# DecadeBox_1.net
KiCad netlist of a schematic drawn in Altium Designer
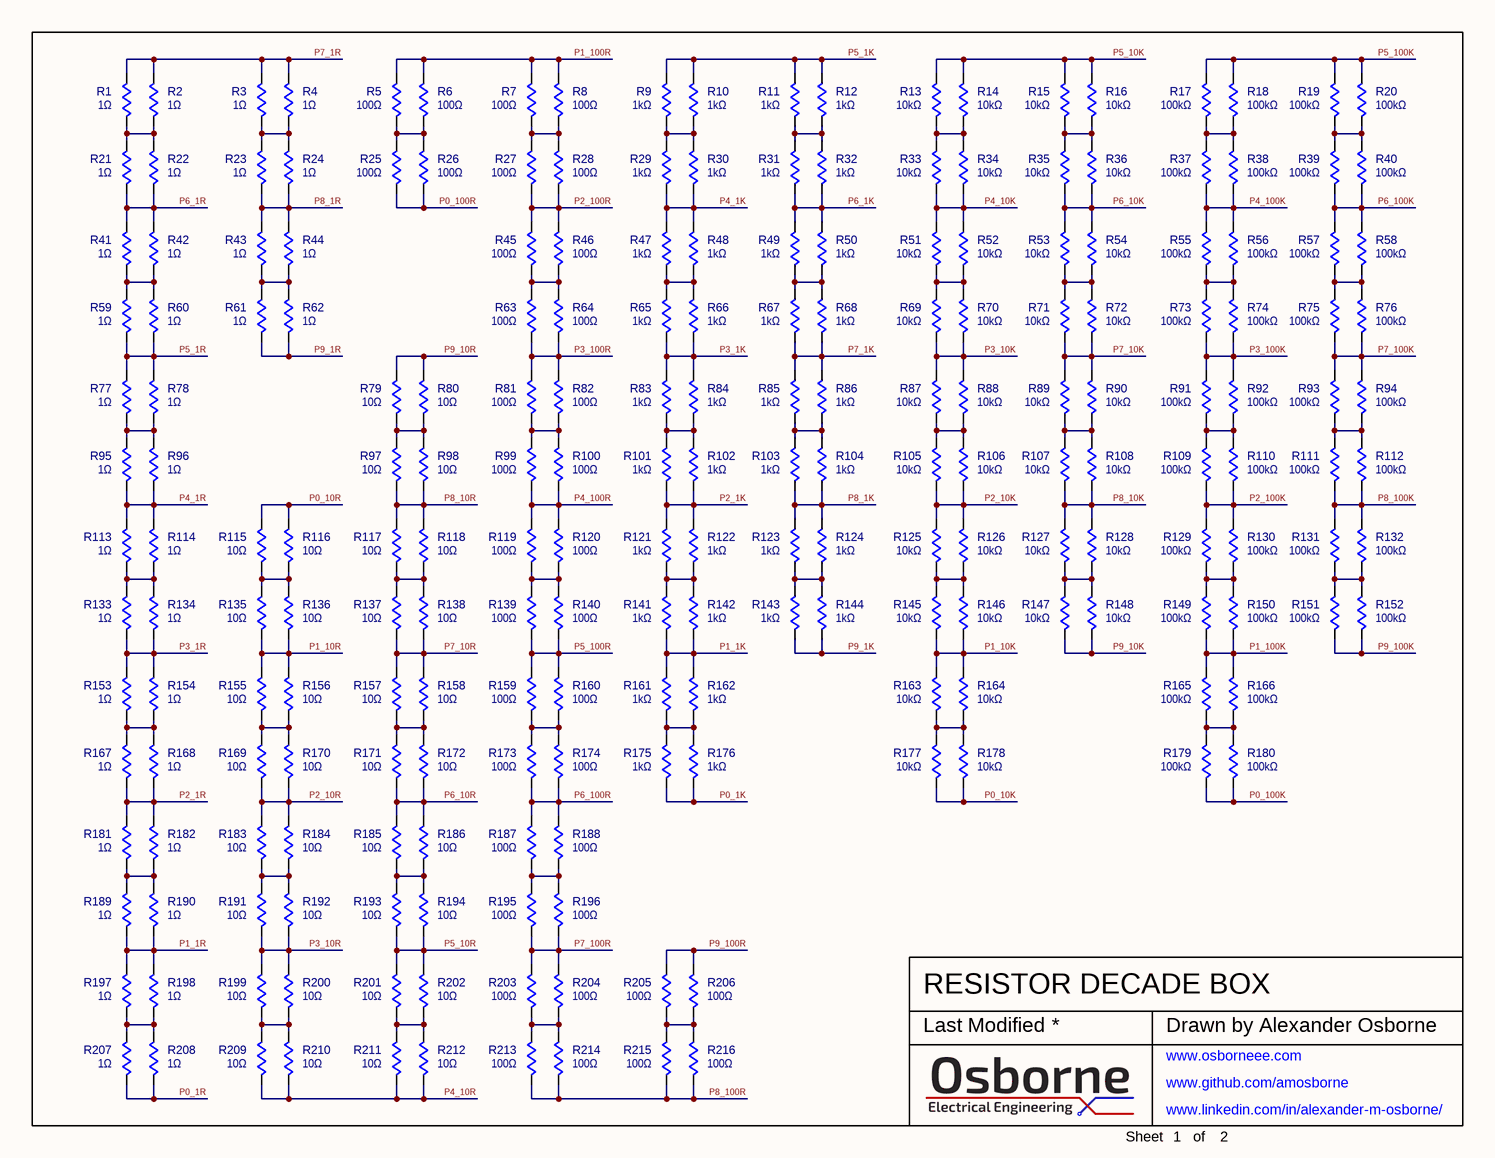
[diagram p0: DecadeBox_1.SchDoc]

(export (version "E")
  (design (tool "Eeschema 10.0.6"))
  (components
    (comp (ref "R1")
      (value "1Ω")
      (footprint "MRS25")
      (description "RES 1Ω 1% 50ppm/K 600mW")
      (fields (field (name "TOLERANCE") "1% + 50ppm/K") (field (name "POWER") "600mW"))
      (libsource (lib "DecadeBox") (part "RES-1OHM"))
    )
    (comp (ref "R2")
      (value "1Ω")
      (footprint "MRS25")
      (description "RES 1Ω 1% 50ppm/K 600mW")
      (fields (field (name "TOLERANCE") "1% + 50ppm/K") (field (name "POWER") "600mW"))
      (libsource (lib "DecadeBox") (part "RES-1OHM"))
    )
    (comp (ref "R3")
      (value "1Ω")
      (footprint "MRS25")
      (description "RES 1Ω 1% 50ppm/K 600mW")
      (fields (field (name "TOLERANCE") "1% + 50ppm/K") (field (name "POWER") "600mW"))
      (libsource (lib "DecadeBox") (part "RES-1OHM"))
    )
    (comp (ref "R4")
      (value "1Ω")
      (footprint "MRS25")
      (description "RES 1Ω 1% 50ppm/K 600mW")
      (fields (field (name "TOLERANCE") "1% + 50ppm/K") (field (name "POWER") "600mW"))
      (libsource (lib "DecadeBox") (part "RES-1OHM"))
    )
    (comp (ref "R5")
      (value "100Ω")
      (footprint "MRS25")
      (description "RES 100Ω 1% 50ppm/K 600mW")
      (fields (field (name "TOLERANCE") "1% + 50ppm/K") (field (name "POWER") "600mW"))
      (libsource (lib "DecadeBox") (part "RES-100OHM"))
    )
    (comp (ref "R6")
      (value "100Ω")
      (footprint "MRS25")
      (description "RES 100Ω 1% 50ppm/K 600mW")
      (fields (field (name "TOLERANCE") "1% + 50ppm/K") (field (name "POWER") "600mW"))
      (libsource (lib "DecadeBox") (part "RES-100OHM"))
    )
    (comp (ref "R7")
      (value "100Ω")
      (footprint "MRS25")
      (description "RES 100Ω 1% 50ppm/K 600mW")
      (fields (field (name "TOLERANCE") "1% + 50ppm/K") (field (name "POWER") "600mW"))
      (libsource (lib "DecadeBox") (part "RES-100OHM"))
    )
    (comp (ref "R8")
      (value "100Ω")
      (footprint "MRS25")
      (description "RES 100Ω 1% 50ppm/K 600mW")
      (fields (field (name "TOLERANCE") "1% + 50ppm/K") (field (name "POWER") "600mW"))
      (libsource (lib "DecadeBox") (part "RES-100OHM"))
    )
    (comp (ref "R9")
      (value "1kΩ")
      (footprint "MRS25")
      (description "RES 1kΩ 1% 50ppm/K 600mW")
      (fields (field (name "TOLERANCE") "1% + 50ppm/K") (field (name "POWER") "600mW"))
      (libsource (lib "DecadeBox") (part "RES-1KOHM"))
    )
    (comp (ref "R10")
      (value "1kΩ")
      (footprint "MRS25")
      (description "RES 1kΩ 1% 50ppm/K 600mW")
      (fields (field (name "TOLERANCE") "1% + 50ppm/K") (field (name "POWER") "600mW"))
      (libsource (lib "DecadeBox") (part "RES-1KOHM"))
    )
    (comp (ref "R11")
      (value "1kΩ")
      (footprint "MRS25")
      (description "RES 1kΩ 1% 50ppm/K 600mW")
      (fields (field (name "TOLERANCE") "1% + 50ppm/K") (field (name "POWER") "600mW"))
      (libsource (lib "DecadeBox") (part "RES-1KOHM"))
    )
    (comp (ref "R12")
      (value "1kΩ")
      (footprint "MRS25")
      (description "RES 1kΩ 1% 50ppm/K 600mW")
      (fields (field (name "TOLERANCE") "1% + 50ppm/K") (field (name "POWER") "600mW"))
      (libsource (lib "DecadeBox") (part "RES-1KOHM"))
    )
    (comp (ref "R13")
      (value "10kΩ")
      (footprint "MRS25")
      (description "RES 10kΩ 1% 50ppm/K 600mW")
      (fields (field (name "TOLERANCE") "1% + 50ppm/K") (field (name "POWER") "600mW"))
      (libsource (lib "DecadeBox") (part "RES-10KOHM"))
    )
    (comp (ref "R14")
      (value "10kΩ")
      (footprint "MRS25")
      (description "RES 10kΩ 1% 50ppm/K 600mW")
      (fields (field (name "TOLERANCE") "1% + 50ppm/K") (field (name "POWER") "600mW"))
      (libsource (lib "DecadeBox") (part "RES-10KOHM"))
    )
    (comp (ref "R15")
      (value "10kΩ")
      (footprint "MRS25")
      (description "RES 10kΩ 1% 50ppm/K 600mW")
      (fields (field (name "TOLERANCE") "1% + 50ppm/K") (field (name "POWER") "600mW"))
      (libsource (lib "DecadeBox") (part "RES-10KOHM"))
    )
    (comp (ref "R16")
      (value "10kΩ")
      (footprint "MRS25")
      (description "RES 10kΩ 1% 50ppm/K 600mW")
      (fields (field (name "TOLERANCE") "1% + 50ppm/K") (field (name "POWER") "600mW"))
      (libsource (lib "DecadeBox") (part "RES-10KOHM"))
    )
    (comp (ref "R17")
      (value "100kΩ")
      (footprint "MRS25")
      (description "RES 100kΩ 1% 50ppm/K 600mW")
      (fields (field (name "TOLERANCE") "1% + 50ppm/K") (field (name "POWER") "600mW"))
      (libsource (lib "DecadeBox") (part "RES-100KOHM"))
    )
    (comp (ref "R18")
      (value "100kΩ")
      (footprint "MRS25")
      (description "RES 100kΩ 1% 50ppm/K 600mW")
      (fields (field (name "TOLERANCE") "1% + 50ppm/K") (field (name "POWER") "600mW"))
      (libsource (lib "DecadeBox") (part "RES-100KOHM"))
    )
    (comp (ref "R19")
      (value "100kΩ")
      (footprint "MRS25")
      (description "RES 100kΩ 1% 50ppm/K 600mW")
      (fields (field (name "TOLERANCE") "1% + 50ppm/K") (field (name "POWER") "600mW"))
      (libsource (lib "DecadeBox") (part "RES-100KOHM"))
    )
    (comp (ref "R20")
      (value "100kΩ")
      (footprint "MRS25")
      (description "RES 100kΩ 1% 50ppm/K 600mW")
      (fields (field (name "TOLERANCE") "1% + 50ppm/K") (field (name "POWER") "600mW"))
      (libsource (lib "DecadeBox") (part "RES-100KOHM"))
    )
    (comp (ref "R21")
      (value "1Ω")
      (footprint "MRS25")
      (description "RES 1Ω 1% 50ppm/K 600mW")
      (fields (field (name "TOLERANCE") "1% + 50ppm/K") (field (name "POWER") "600mW"))
      (libsource (lib "DecadeBox") (part "RES-1OHM"))
    )
    (comp (ref "R22")
      (value "1Ω")
      (footprint "MRS25")
      (description "RES 1Ω 1% 50ppm/K 600mW")
      (fields (field (name "TOLERANCE") "1% + 50ppm/K") (field (name "POWER") "600mW"))
      (libsource (lib "DecadeBox") (part "RES-1OHM"))
    )
    (comp (ref "R23")
      (value "1Ω")
      (footprint "MRS25")
      (description "RES 1Ω 1% 50ppm/K 600mW")
      (fields (field (name "TOLERANCE") "1% + 50ppm/K") (field (name "POWER") "600mW"))
      (libsource (lib "DecadeBox") (part "RES-1OHM"))
    )
    (comp (ref "R24")
      (value "1Ω")
      (footprint "MRS25")
      (description "RES 1Ω 1% 50ppm/K 600mW")
      (fields (field (name "TOLERANCE") "1% + 50ppm/K") (field (name "POWER") "600mW"))
      (libsource (lib "DecadeBox") (part "RES-1OHM"))
    )
    (comp (ref "R25")
      (value "100Ω")
      (footprint "MRS25")
      (description "RES 100Ω 1% 50ppm/K 600mW")
      (fields (field (name "TOLERANCE") "1% + 50ppm/K") (field (name "POWER") "600mW"))
      (libsource (lib "DecadeBox") (part "RES-100OHM"))
    )
    (comp (ref "R26")
      (value "100Ω")
      (footprint "MRS25")
      (description "RES 100Ω 1% 50ppm/K 600mW")
      (fields (field (name "TOLERANCE") "1% + 50ppm/K") (field (name "POWER") "600mW"))
      (libsource (lib "DecadeBox") (part "RES-100OHM"))
    )
    (comp (ref "R27")
      (value "100Ω")
      (footprint "MRS25")
      (description "RES 100Ω 1% 50ppm/K 600mW")
      (fields (field (name "TOLERANCE") "1% + 50ppm/K") (field (name "POWER") "600mW"))
      (libsource (lib "DecadeBox") (part "RES-100OHM"))
    )
    (comp (ref "R28")
      (value "100Ω")
      (footprint "MRS25")
      (description "RES 100Ω 1% 50ppm/K 600mW")
      (fields (field (name "TOLERANCE") "1% + 50ppm/K") (field (name "POWER") "600mW"))
      (libsource (lib "DecadeBox") (part "RES-100OHM"))
    )
    (comp (ref "R29")
      (value "1kΩ")
      (footprint "MRS25")
      (description "RES 1kΩ 1% 50ppm/K 600mW")
      (fields (field (name "TOLERANCE") "1% + 50ppm/K") (field (name "POWER") "600mW"))
      (libsource (lib "DecadeBox") (part "RES-1KOHM"))
    )
    (comp (ref "R30")
      (value "1kΩ")
      (footprint "MRS25")
      (description "RES 1kΩ 1% 50ppm/K 600mW")
      (fields (field (name "TOLERANCE") "1% + 50ppm/K") (field (name "POWER") "600mW"))
      (libsource (lib "DecadeBox") (part "RES-1KOHM"))
    )
    (comp (ref "R31")
      (value "1kΩ")
      (footprint "MRS25")
      (description "RES 1kΩ 1% 50ppm/K 600mW")
      (fields (field (name "TOLERANCE") "1% + 50ppm/K") (field (name "POWER") "600mW"))
      (libsource (lib "DecadeBox") (part "RES-1KOHM"))
    )
    (comp (ref "R32")
      (value "1kΩ")
      (footprint "MRS25")
      (description "RES 1kΩ 1% 50ppm/K 600mW")
      (fields (field (name "TOLERANCE") "1% + 50ppm/K") (field (name "POWER") "600mW"))
      (libsource (lib "DecadeBox") (part "RES-1KOHM"))
    )
    (comp (ref "R33")
      (value "10kΩ")
      (footprint "MRS25")
      (description "RES 10kΩ 1% 50ppm/K 600mW")
      (fields (field (name "TOLERANCE") "1% + 50ppm/K") (field (name "POWER") "600mW"))
      (libsource (lib "DecadeBox") (part "RES-10KOHM"))
    )
    (comp (ref "R34")
      (value "10kΩ")
      (footprint "MRS25")
      (description "RES 10kΩ 1% 50ppm/K 600mW")
      (fields (field (name "TOLERANCE") "1% + 50ppm/K") (field (name "POWER") "600mW"))
      (libsource (lib "DecadeBox") (part "RES-10KOHM"))
    )
    (comp (ref "R35")
      (value "10kΩ")
      (footprint "MRS25")
      (description "RES 10kΩ 1% 50ppm/K 600mW")
      (fields (field (name "TOLERANCE") "1% + 50ppm/K") (field (name "POWER") "600mW"))
      (libsource (lib "DecadeBox") (part "RES-10KOHM"))
    )
    (comp (ref "R36")
      (value "10kΩ")
      (footprint "MRS25")
      (description "RES 10kΩ 1% 50ppm/K 600mW")
      (fields (field (name "TOLERANCE") "1% + 50ppm/K") (field (name "POWER") "600mW"))
      (libsource (lib "DecadeBox") (part "RES-10KOHM"))
    )
    (comp (ref "R37")
      (value "100kΩ")
      (footprint "MRS25")
      (description "RES 100kΩ 1% 50ppm/K 600mW")
      (fields (field (name "TOLERANCE") "1% + 50ppm/K") (field (name "POWER") "600mW"))
      (libsource (lib "DecadeBox") (part "RES-100KOHM"))
    )
    (comp (ref "R38")
      (value "100kΩ")
      (footprint "MRS25")
      (description "RES 100kΩ 1% 50ppm/K 600mW")
      (fields (field (name "TOLERANCE") "1% + 50ppm/K") (field (name "POWER") "600mW"))
      (libsource (lib "DecadeBox") (part "RES-100KOHM"))
    )
    (comp (ref "R39")
      (value "100kΩ")
      (footprint "MRS25")
      (description "RES 100kΩ 1% 50ppm/K 600mW")
      (fields (field (name "TOLERANCE") "1% + 50ppm/K") (field (name "POWER") "600mW"))
      (libsource (lib "DecadeBox") (part "RES-100KOHM"))
    )
    (comp (ref "R40")
      (value "100kΩ")
      (footprint "MRS25")
      (description "RES 100kΩ 1% 50ppm/K 600mW")
      (fields (field (name "TOLERANCE") "1% + 50ppm/K") (field (name "POWER") "600mW"))
      (libsource (lib "DecadeBox") (part "RES-100KOHM"))
    )
    (comp (ref "R41")
      (value "1Ω")
      (footprint "MRS25")
      (description "RES 1Ω 1% 50ppm/K 600mW")
      (fields (field (name "TOLERANCE") "1% + 50ppm/K") (field (name "POWER") "600mW"))
      (libsource (lib "DecadeBox") (part "RES-1OHM"))
    )
    (comp (ref "R42")
      (value "1Ω")
      (footprint "MRS25")
      (description "RES 1Ω 1% 50ppm/K 600mW")
      (fields (field (name "TOLERANCE") "1% + 50ppm/K") (field (name "POWER") "600mW"))
      (libsource (lib "DecadeBox") (part "RES-1OHM"))
    )
    (comp (ref "R43")
      (value "1Ω")
      (footprint "MRS25")
      (description "RES 1Ω 1% 50ppm/K 600mW")
      (fields (field (name "TOLERANCE") "1% + 50ppm/K") (field (name "POWER") "600mW"))
      (libsource (lib "DecadeBox") (part "RES-1OHM"))
    )
    (comp (ref "R44")
      (value "1Ω")
      (footprint "MRS25")
      (description "RES 1Ω 1% 50ppm/K 600mW")
      (fields (field (name "TOLERANCE") "1% + 50ppm/K") (field (name "POWER") "600mW"))
      (libsource (lib "DecadeBox") (part "RES-1OHM"))
    )
    (comp (ref "R45")
      (value "100Ω")
      (footprint "MRS25")
      (description "RES 100Ω 1% 50ppm/K 600mW")
      (fields (field (name "TOLERANCE") "1% + 50ppm/K") (field (name "POWER") "600mW"))
      (libsource (lib "DecadeBox") (part "RES-100OHM"))
    )
    (comp (ref "R46")
      (value "100Ω")
      (footprint "MRS25")
      (description "RES 100Ω 1% 50ppm/K 600mW")
      (fields (field (name "TOLERANCE") "1% + 50ppm/K") (field (name "POWER") "600mW"))
      (libsource (lib "DecadeBox") (part "RES-100OHM"))
    )
    (comp (ref "R47")
      (value "1kΩ")
      (footprint "MRS25")
      (description "RES 1kΩ 1% 50ppm/K 600mW")
      (fields (field (name "TOLERANCE") "1% + 50ppm/K") (field (name "POWER") "600mW"))
      (libsource (lib "DecadeBox") (part "RES-1KOHM"))
    )
    (comp (ref "R48")
      (value "1kΩ")
      (footprint "MRS25")
      (description "RES 1kΩ 1% 50ppm/K 600mW")
      (fields (field (name "TOLERANCE") "1% + 50ppm/K") (field (name "POWER") "600mW"))
      (libsource (lib "DecadeBox") (part "RES-1KOHM"))
    )
    (comp (ref "R49")
      (value "1kΩ")
      (footprint "MRS25")
      (description "RES 1kΩ 1% 50ppm/K 600mW")
      (fields (field (name "TOLERANCE") "1% + 50ppm/K") (field (name "POWER") "600mW"))
      (libsource (lib "DecadeBox") (part "RES-1KOHM"))
    )
    (comp (ref "R50")
      (value "1kΩ")
      (footprint "MRS25")
      (description "RES 1kΩ 1% 50ppm/K 600mW")
      (fields (field (name "TOLERANCE") "1% + 50ppm/K") (field (name "POWER") "600mW"))
      (libsource (lib "DecadeBox") (part "RES-1KOHM"))
    )
    (comp (ref "R51")
      (value "10kΩ")
      (footprint "MRS25")
      (description "RES 10kΩ 1% 50ppm/K 600mW")
      (fields (field (name "TOLERANCE") "1% + 50ppm/K") (field (name "POWER") "600mW"))
      (libsource (lib "DecadeBox") (part "RES-10KOHM"))
    )
    (comp (ref "R52")
      (value "10kΩ")
      (footprint "MRS25")
      (description "RES 10kΩ 1% 50ppm/K 600mW")
      (fields (field (name "TOLERANCE") "1% + 50ppm/K") (field (name "POWER") "600mW"))
      (libsource (lib "DecadeBox") (part "RES-10KOHM"))
    )
    (comp (ref "R53")
      (value "10kΩ")
      (footprint "MRS25")
      (description "RES 10kΩ 1% 50ppm/K 600mW")
      (fields (field (name "TOLERANCE") "1% + 50ppm/K") (field (name "POWER") "600mW"))
      (libsource (lib "DecadeBox") (part "RES-10KOHM"))
    )
    (comp (ref "R54")
      (value "10kΩ")
      (footprint "MRS25")
      (description "RES 10kΩ 1% 50ppm/K 600mW")
      (fields (field (name "TOLERANCE") "1% + 50ppm/K") (field (name "POWER") "600mW"))
      (libsource (lib "DecadeBox") (part "RES-10KOHM"))
    )
    (comp (ref "R55")
      (value "100kΩ")
      (footprint "MRS25")
      (description "RES 100kΩ 1% 50ppm/K 600mW")
      (fields (field (name "TOLERANCE") "1% + 50ppm/K") (field (name "POWER") "600mW"))
      (libsource (lib "DecadeBox") (part "RES-100KOHM"))
    )
    (comp (ref "R56")
      (value "100kΩ")
      (footprint "MRS25")
      (description "RES 100kΩ 1% 50ppm/K 600mW")
      (fields (field (name "TOLERANCE") "1% + 50ppm/K") (field (name "POWER") "600mW"))
      (libsource (lib "DecadeBox") (part "RES-100KOHM"))
    )
    (comp (ref "R57")
      (value "100kΩ")
      (footprint "MRS25")
      (description "RES 100kΩ 1% 50ppm/K 600mW")
      (fields (field (name "TOLERANCE") "1% + 50ppm/K") (field (name "POWER") "600mW"))
      (libsource (lib "DecadeBox") (part "RES-100KOHM"))
    )
    (comp (ref "R58")
      (value "100kΩ")
      (footprint "MRS25")
      (description "RES 100kΩ 1% 50ppm/K 600mW")
      (fields (field (name "TOLERANCE") "1% + 50ppm/K") (field (name "POWER") "600mW"))
      (libsource (lib "DecadeBox") (part "RES-100KOHM"))
    )
    (comp (ref "R59")
      (value "1Ω")
      (footprint "MRS25")
      (description "RES 1Ω 1% 50ppm/K 600mW")
      (fields (field (name "TOLERANCE") "1% + 50ppm/K") (field (name "POWER") "600mW"))
      (libsource (lib "DecadeBox") (part "RES-1OHM"))
    )
    (comp (ref "R60")
      (value "1Ω")
      (footprint "MRS25")
      (description "RES 1Ω 1% 50ppm/K 600mW")
      (fields (field (name "TOLERANCE") "1% + 50ppm/K") (field (name "POWER") "600mW"))
      (libsource (lib "DecadeBox") (part "RES-1OHM"))
    )
    (comp (ref "R61")
      (value "1Ω")
      (footprint "MRS25")
      (description "RES 1Ω 1% 50ppm/K 600mW")
      (fields (field (name "TOLERANCE") "1% + 50ppm/K") (field (name "POWER") "600mW"))
      (libsource (lib "DecadeBox") (part "RES-1OHM"))
    )
    (comp (ref "R62")
      (value "1Ω")
      (footprint "MRS25")
      (description "RES 1Ω 1% 50ppm/K 600mW")
      (fields (field (name "TOLERANCE") "1% + 50ppm/K") (field (name "POWER") "600mW"))
      (libsource (lib "DecadeBox") (part "RES-1OHM"))
    )
    (comp (ref "R63")
      (value "100Ω")
      (footprint "MRS25")
      (description "RES 100Ω 1% 50ppm/K 600mW")
      (fields (field (name "TOLERANCE") "1% + 50ppm/K") (field (name "POWER") "600mW"))
      (libsource (lib "DecadeBox") (part "RES-100OHM"))
    )
    (comp (ref "R64")
      (value "100Ω")
      (footprint "MRS25")
      (description "RES 100Ω 1% 50ppm/K 600mW")
      (fields (field (name "TOLERANCE") "1% + 50ppm/K") (field (name "POWER") "600mW"))
      (libsource (lib "DecadeBox") (part "RES-100OHM"))
    )
    (comp (ref "R65")
      (value "1kΩ")
      (footprint "MRS25")
      (description "RES 1kΩ 1% 50ppm/K 600mW")
      (fields (field (name "TOLERANCE") "1% + 50ppm/K") (field (name "POWER") "600mW"))
      (libsource (lib "DecadeBox") (part "RES-1KOHM"))
    )
    (comp (ref "R66")
      (value "1kΩ")
      (footprint "MRS25")
      (description "RES 1kΩ 1% 50ppm/K 600mW")
      (fields (field (name "TOLERANCE") "1% + 50ppm/K") (field (name "POWER") "600mW"))
      (libsource (lib "DecadeBox") (part "RES-1KOHM"))
    )
    (comp (ref "R67")
      (value "1kΩ")
      (footprint "MRS25")
      (description "RES 1kΩ 1% 50ppm/K 600mW")
      (fields (field (name "TOLERANCE") "1% + 50ppm/K") (field (name "POWER") "600mW"))
      (libsource (lib "DecadeBox") (part "RES-1KOHM"))
    )
    (comp (ref "R68")
      (value "1kΩ")
      (footprint "MRS25")
      (description "RES 1kΩ 1% 50ppm/K 600mW")
      (fields (field (name "TOLERANCE") "1% + 50ppm/K") (field (name "POWER") "600mW"))
      (libsource (lib "DecadeBox") (part "RES-1KOHM"))
    )
    (comp (ref "R69")
      (value "10kΩ")
      (footprint "MRS25")
      (description "RES 10kΩ 1% 50ppm/K 600mW")
      (fields (field (name "TOLERANCE") "1% + 50ppm/K") (field (name "POWER") "600mW"))
      (libsource (lib "DecadeBox") (part "RES-10KOHM"))
    )
    (comp (ref "R70")
      (value "10kΩ")
      (footprint "MRS25")
      (description "RES 10kΩ 1% 50ppm/K 600mW")
      (fields (field (name "TOLERANCE") "1% + 50ppm/K") (field (name "POWER") "600mW"))
      (libsource (lib "DecadeBox") (part "RES-10KOHM"))
    )
    (comp (ref "R71")
      (value "10kΩ")
      (footprint "MRS25")
      (description "RES 10kΩ 1% 50ppm/K 600mW")
      (fields (field (name "TOLERANCE") "1% + 50ppm/K") (field (name "POWER") "600mW"))
      (libsource (lib "DecadeBox") (part "RES-10KOHM"))
    )
    (comp (ref "R72")
      (value "10kΩ")
      (footprint "MRS25")
      (description "RES 10kΩ 1% 50ppm/K 600mW")
      (fields (field (name "TOLERANCE") "1% + 50ppm/K") (field (name "POWER") "600mW"))
      (libsource (lib "DecadeBox") (part "RES-10KOHM"))
    )
    (comp (ref "R73")
      (value "100kΩ")
      (footprint "MRS25")
      (description "RES 100kΩ 1% 50ppm/K 600mW")
      (fields (field (name "TOLERANCE") "1% + 50ppm/K") (field (name "POWER") "600mW"))
      (libsource (lib "DecadeBox") (part "RES-100KOHM"))
    )
    (comp (ref "R74")
      (value "100kΩ")
      (footprint "MRS25")
      (description "RES 100kΩ 1% 50ppm/K 600mW")
      (fields (field (name "TOLERANCE") "1% + 50ppm/K") (field (name "POWER") "600mW"))
      (libsource (lib "DecadeBox") (part "RES-100KOHM"))
    )
    (comp (ref "R75")
      (value "100kΩ")
      (footprint "MRS25")
      (description "RES 100kΩ 1% 50ppm/K 600mW")
      (fields (field (name "TOLERANCE") "1% + 50ppm/K") (field (name "POWER") "600mW"))
      (libsource (lib "DecadeBox") (part "RES-100KOHM"))
    )
    (comp (ref "R76")
      (value "100kΩ")
      (footprint "MRS25")
      (description "RES 100kΩ 1% 50ppm/K 600mW")
      (fields (field (name "TOLERANCE") "1% + 50ppm/K") (field (name "POWER") "600mW"))
      (libsource (lib "DecadeBox") (part "RES-100KOHM"))
    )
    (comp (ref "R77")
      (value "1Ω")
      (footprint "MRS25")
      (description "RES 1Ω 1% 50ppm/K 600mW")
      (fields (field (name "TOLERANCE") "1% + 50ppm/K") (field (name "POWER") "600mW"))
      (libsource (lib "DecadeBox") (part "RES-1OHM"))
    )
    (comp (ref "R78")
      (value "1Ω")
      (footprint "MRS25")
      (description "RES 1Ω 1% 50ppm/K 600mW")
      (fields (field (name "TOLERANCE") "1% + 50ppm/K") (field (name "POWER") "600mW"))
      (libsource (lib "DecadeBox") (part "RES-1OHM"))
    )
    (comp (ref "R79")
      (value "10Ω")
      (footprint "MRS25")
      (description "RES 10Ω 1% 50ppm/K 600mW")
      (fields (field (name "TOLERANCE") "1% + 50ppm/K") (field (name "POWER") "600mW"))
      (libsource (lib "DecadeBox") (part "RES-10OHM"))
    )
    (comp (ref "R80")
      (value "10Ω")
      (footprint "MRS25")
      (description "RES 10Ω 1% 50ppm/K 600mW")
      (fields (field (name "TOLERANCE") "1% + 50ppm/K") (field (name "POWER") "600mW"))
      (libsource (lib "DecadeBox") (part "RES-10OHM"))
    )
    (comp (ref "R81")
      (value "100Ω")
      (footprint "MRS25")
      (description "RES 100Ω 1% 50ppm/K 600mW")
      (fields (field (name "TOLERANCE") "1% + 50ppm/K") (field (name "POWER") "600mW"))
      (libsource (lib "DecadeBox") (part "RES-100OHM"))
    )
    (comp (ref "R82")
      (value "100Ω")
      (footprint "MRS25")
      (description "RES 100Ω 1% 50ppm/K 600mW")
      (fields (field (name "TOLERANCE") "1% + 50ppm/K") (field (name "POWER") "600mW"))
      (libsource (lib "DecadeBox") (part "RES-100OHM"))
    )
    (comp (ref "R83")
      (value "1kΩ")
      (footprint "MRS25")
      (description "RES 1kΩ 1% 50ppm/K 600mW")
      (fields (field (name "TOLERANCE") "1% + 50ppm/K") (field (name "POWER") "600mW"))
      (libsource (lib "DecadeBox") (part "RES-1KOHM"))
    )
    (comp (ref "R84")
      (value "1kΩ")
      (footprint "MRS25")
      (description "RES 1kΩ 1% 50ppm/K 600mW")
      (fields (field (name "TOLERANCE") "1% + 50ppm/K") (field (name "POWER") "600mW"))
      (libsource (lib "DecadeBox") (part "RES-1KOHM"))
    )
    (comp (ref "R85")
      (value "1kΩ")
      (footprint "MRS25")
      (description "RES 1kΩ 1% 50ppm/K 600mW")
      (fields (field (name "TOLERANCE") "1% + 50ppm/K") (field (name "POWER") "600mW"))
      (libsource (lib "DecadeBox") (part "RES-1KOHM"))
    )
    (comp (ref "R86")
      (value "1kΩ")
      (footprint "MRS25")
      (description "RES 1kΩ 1% 50ppm/K 600mW")
      (fields (field (name "TOLERANCE") "1% + 50ppm/K") (field (name "POWER") "600mW"))
      (libsource (lib "DecadeBox") (part "RES-1KOHM"))
    )
    (comp (ref "R87")
      (value "10kΩ")
      (footprint "MRS25")
      (description "RES 10kΩ 1% 50ppm/K 600mW")
      (fields (field (name "TOLERANCE") "1% + 50ppm/K") (field (name "POWER") "600mW"))
      (libsource (lib "DecadeBox") (part "RES-10KOHM"))
    )
    (comp (ref "R88")
      (value "10kΩ")
      (footprint "MRS25")
      (description "RES 10kΩ 1% 50ppm/K 600mW")
      (fields (field (name "TOLERANCE") "1% + 50ppm/K") (field (name "POWER") "600mW"))
      (libsource (lib "DecadeBox") (part "RES-10KOHM"))
    )
    (comp (ref "R89")
      (value "10kΩ")
      (footprint "MRS25")
      (description "RES 10kΩ 1% 50ppm/K 600mW")
      (fields (field (name "TOLERANCE") "1% + 50ppm/K") (field (name "POWER") "600mW"))
      (libsource (lib "DecadeBox") (part "RES-10KOHM"))
    )
    (comp (ref "R90")
      (value "10kΩ")
      (footprint "MRS25")
      (description "RES 10kΩ 1% 50ppm/K 600mW")
      (fields (field (name "TOLERANCE") "1% + 50ppm/K") (field (name "POWER") "600mW"))
      (libsource (lib "DecadeBox") (part "RES-10KOHM"))
    )
    (comp (ref "R91")
      (value "100kΩ")
      (footprint "MRS25")
      (description "RES 100kΩ 1% 50ppm/K 600mW")
      (fields (field (name "TOLERANCE") "1% + 50ppm/K") (field (name "POWER") "600mW"))
      (libsource (lib "DecadeBox") (part "RES-100KOHM"))
    )
    (comp (ref "R92")
      (value "100kΩ")
      (footprint "MRS25")
      (description "RES 100kΩ 1% 50ppm/K 600mW")
      (fields (field (name "TOLERANCE") "1% + 50ppm/K") (field (name "POWER") "600mW"))
      (libsource (lib "DecadeBox") (part "RES-100KOHM"))
    )
    (comp (ref "R93")
      (value "100kΩ")
      (footprint "MRS25")
      (description "RES 100kΩ 1% 50ppm/K 600mW")
      (fields (field (name "TOLERANCE") "1% + 50ppm/K") (field (name "POWER") "600mW"))
      (libsource (lib "DecadeBox") (part "RES-100KOHM"))
    )
    (comp (ref "R94")
      (value "100kΩ")
      (footprint "MRS25")
      (description "RES 100kΩ 1% 50ppm/K 600mW")
      (fields (field (name "TOLERANCE") "1% + 50ppm/K") (field (name "POWER") "600mW"))
      (libsource (lib "DecadeBox") (part "RES-100KOHM"))
    )
    (comp (ref "R95")
      (value "1Ω")
      (footprint "MRS25")
      (description "RES 1Ω 1% 50ppm/K 600mW")
      (fields (field (name "TOLERANCE") "1% + 50ppm/K") (field (name "POWER") "600mW"))
      (libsource (lib "DecadeBox") (part "RES-1OHM"))
    )
    (comp (ref "R96")
      (value "1Ω")
      (footprint "MRS25")
      (description "RES 1Ω 1% 50ppm/K 600mW")
      (fields (field (name "TOLERANCE") "1% + 50ppm/K") (field (name "POWER") "600mW"))
      (libsource (lib "DecadeBox") (part "RES-1OHM"))
    )
    (comp (ref "R97")
      (value "10Ω")
      (footprint "MRS25")
      (description "RES 10Ω 1% 50ppm/K 600mW")
      (fields (field (name "TOLERANCE") "1% + 50ppm/K") (field (name "POWER") "600mW"))
      (libsource (lib "DecadeBox") (part "RES-10OHM"))
    )
    (comp (ref "R98")
      (value "10Ω")
      (footprint "MRS25")
      (description "RES 10Ω 1% 50ppm/K 600mW")
      (fields (field (name "TOLERANCE") "1% + 50ppm/K") (field (name "POWER") "600mW"))
      (libsource (lib "DecadeBox") (part "RES-10OHM"))
    )
    (comp (ref "R99")
      (value "100Ω")
      (footprint "MRS25")
      (description "RES 100Ω 1% 50ppm/K 600mW")
      (fields (field (name "TOLERANCE") "1% + 50ppm/K") (field (name "POWER") "600mW"))
      (libsource (lib "DecadeBox") (part "RES-100OHM"))
    )
    (comp (ref "R100")
      (value "100Ω")
      (footprint "MRS25")
      (description "RES 100Ω 1% 50ppm/K 600mW")
      (fields (field (name "TOLERANCE") "1% + 50ppm/K") (field (name "POWER") "600mW"))
      (libsource (lib "DecadeBox") (part "RES-100OHM"))
    )
    (comp (ref "R101")
      (value "1kΩ")
      (footprint "MRS25")
      (description "RES 1kΩ 1% 50ppm/K 600mW")
      (fields (field (name "TOLERANCE") "1% + 50ppm/K") (field (name "POWER") "600mW"))
      (libsource (lib "DecadeBox") (part "RES-1KOHM"))
    )
    (comp (ref "R102")
      (value "1kΩ")
      (footprint "MRS25")
      (description "RES 1kΩ 1% 50ppm/K 600mW")
      (fields (field (name "TOLERANCE") "1% + 50ppm/K") (field (name "POWER") "600mW"))
      (libsource (lib "DecadeBox") (part "RES-1KOHM"))
    )
    (comp (ref "R103")
      (value "1kΩ")
      (footprint "MRS25")
      (description "RES 1kΩ 1% 50ppm/K 600mW")
      (fields (field (name "TOLERANCE") "1% + 50ppm/K") (field (name "POWER") "600mW"))
      (libsource (lib "DecadeBox") (part "RES-1KOHM"))
    )
    (comp (ref "R104")
      (value "1kΩ")
      (footprint "MRS25")
      (description "RES 1kΩ 1% 50ppm/K 600mW")
      (fields (field (name "TOLERANCE") "1% + 50ppm/K") (field (name "POWER") "600mW"))
      (libsource (lib "DecadeBox") (part "RES-1KOHM"))
    )
    (comp (ref "R105")
      (value "10kΩ")
      (footprint "MRS25")
      (description "RES 10kΩ 1% 50ppm/K 600mW")
      (fields (field (name "TOLERANCE") "1% + 50ppm/K") (field (name "POWER") "600mW"))
      (libsource (lib "DecadeBox") (part "RES-10KOHM"))
    )
    (comp (ref "R106")
      (value "10kΩ")
      (footprint "MRS25")
      (description "RES 10kΩ 1% 50ppm/K 600mW")
      (fields (field (name "TOLERANCE") "1% + 50ppm/K") (field (name "POWER") "600mW"))
      (libsource (lib "DecadeBox") (part "RES-10KOHM"))
    )
    (comp (ref "R107")
      (value "10kΩ")
      (footprint "MRS25")
      (description "RES 10kΩ 1% 50ppm/K 600mW")
      (fields (field (name "TOLERANCE") "1% + 50ppm/K") (field (name "POWER") "600mW"))
      (libsource (lib "DecadeBox") (part "RES-10KOHM"))
    )
    (comp (ref "R108")
      (value "10kΩ")
      (footprint "MRS25")
      (description "RES 10kΩ 1% 50ppm/K 600mW")
      (fields (field (name "TOLERANCE") "1% + 50ppm/K") (field (name "POWER") "600mW"))
      (libsource (lib "DecadeBox") (part "RES-10KOHM"))
    )
    (comp (ref "R109")
      (value "100kΩ")
      (footprint "MRS25")
      (description "RES 100kΩ 1% 50ppm/K 600mW")
      (fields (field (name "TOLERANCE") "1% + 50ppm/K") (field (name "POWER") "600mW"))
      (libsource (lib "DecadeBox") (part "RES-100KOHM"))
    )
    (comp (ref "R110")
      (value "100kΩ")
      (footprint "MRS25")
      (description "RES 100kΩ 1% 50ppm/K 600mW")
      (fields (field (name "TOLERANCE") "1% + 50ppm/K") (field (name "POWER") "600mW"))
      (libsource (lib "DecadeBox") (part "RES-100KOHM"))
    )
    (comp (ref "R111")
      (value "100kΩ")
      (footprint "MRS25")
      (description "RES 100kΩ 1% 50ppm/K 600mW")
      (fields (field (name "TOLERANCE") "1% + 50ppm/K") (field (name "POWER") "600mW"))
      (libsource (lib "DecadeBox") (part "RES-100KOHM"))
    )
    (comp (ref "R112")
      (value "100kΩ")
      (footprint "MRS25")
      (description "RES 100kΩ 1% 50ppm/K 600mW")
      (fields (field (name "TOLERANCE") "1% + 50ppm/K") (field (name "POWER") "600mW"))
      (libsource (lib "DecadeBox") (part "RES-100KOHM"))
    )
    (comp (ref "R113")
      (value "1Ω")
      (footprint "MRS25")
      (description "RES 1Ω 1% 50ppm/K 600mW")
      (fields (field (name "TOLERANCE") "1% + 50ppm/K") (field (name "POWER") "600mW"))
      (libsource (lib "DecadeBox") (part "RES-1OHM"))
    )
    (comp (ref "R114")
      (value "1Ω")
      (footprint "MRS25")
      (description "RES 1Ω 1% 50ppm/K 600mW")
      (fields (field (name "TOLERANCE") "1% + 50ppm/K") (field (name "POWER") "600mW"))
      (libsource (lib "DecadeBox") (part "RES-1OHM"))
    )
    (comp (ref "R115")
      (value "10Ω")
      (footprint "MRS25")
      (description "RES 10Ω 1% 50ppm/K 600mW")
      (fields (field (name "TOLERANCE") "1% + 50ppm/K") (field (name "POWER") "600mW"))
      (libsource (lib "DecadeBox") (part "RES-10OHM"))
    )
    (comp (ref "R116")
      (value "10Ω")
      (footprint "MRS25")
      (description "RES 10Ω 1% 50ppm/K 600mW")
      (fields (field (name "TOLERANCE") "1% + 50ppm/K") (field (name "POWER") "600mW"))
      (libsource (lib "DecadeBox") (part "RES-10OHM"))
    )
    (comp (ref "R117")
      (value "10Ω")
      (footprint "MRS25")
      (description "RES 10Ω 1% 50ppm/K 600mW")
      (fields (field (name "TOLERANCE") "1% + 50ppm/K") (field (name "POWER") "600mW"))
      (libsource (lib "DecadeBox") (part "RES-10OHM"))
    )
    (comp (ref "R118")
      (value "10Ω")
      (footprint "MRS25")
      (description "RES 10Ω 1% 50ppm/K 600mW")
      (fields (field (name "TOLERANCE") "1% + 50ppm/K") (field (name "POWER") "600mW"))
      (libsource (lib "DecadeBox") (part "RES-10OHM"))
    )
    (comp (ref "R119")
      (value "100Ω")
      (footprint "MRS25")
      (description "RES 100Ω 1% 50ppm/K 600mW")
      (fields (field (name "TOLERANCE") "1% + 50ppm/K") (field (name "POWER") "600mW"))
      (libsource (lib "DecadeBox") (part "RES-100OHM"))
    )
    (comp (ref "R120")
      (value "100Ω")
      (footprint "MRS25")
      (description "RES 100Ω 1% 50ppm/K 600mW")
      (fields (field (name "TOLERANCE") "1% + 50ppm/K") (field (name "POWER") "600mW"))
      (libsource (lib "DecadeBox") (part "RES-100OHM"))
    )
    (comp (ref "R121")
      (value "1kΩ")
      (footprint "MRS25")
      (description "RES 1kΩ 1% 50ppm/K 600mW")
      (fields (field (name "TOLERANCE") "1% + 50ppm/K") (field (name "POWER") "600mW"))
      (libsource (lib "DecadeBox") (part "RES-1KOHM"))
    )
    (comp (ref "R122")
      (value "1kΩ")
      (footprint "MRS25")
      (description "RES 1kΩ 1% 50ppm/K 600mW")
      (fields (field (name "TOLERANCE") "1% + 50ppm/K") (field (name "POWER") "600mW"))
      (libsource (lib "DecadeBox") (part "RES-1KOHM"))
    )
    (comp (ref "R123")
      (value "1kΩ")
      (footprint "MRS25")
      (description "RES 1kΩ 1% 50ppm/K 600mW")
      (fields (field (name "TOLERANCE") "1% + 50ppm/K") (field (name "POWER") "600mW"))
      (libsource (lib "DecadeBox") (part "RES-1KOHM"))
    )
    (comp (ref "R124")
      (value "1kΩ")
      (footprint "MRS25")
      (description "RES 1kΩ 1% 50ppm/K 600mW")
      (fields (field (name "TOLERANCE") "1% + 50ppm/K") (field (name "POWER") "600mW"))
      (libsource (lib "DecadeBox") (part "RES-1KOHM"))
    )
    (comp (ref "R125")
      (value "10kΩ")
      (footprint "MRS25")
      (description "RES 10kΩ 1% 50ppm/K 600mW")
      (fields (field (name "TOLERANCE") "1% + 50ppm/K") (field (name "POWER") "600mW"))
      (libsource (lib "DecadeBox") (part "RES-10KOHM"))
    )
    (comp (ref "R126")
      (value "10kΩ")
      (footprint "MRS25")
      (description "RES 10kΩ 1% 50ppm/K 600mW")
      (fields (field (name "TOLERANCE") "1% + 50ppm/K") (field (name "POWER") "600mW"))
      (libsource (lib "DecadeBox") (part "RES-10KOHM"))
    )
    (comp (ref "R127")
      (value "10kΩ")
      (footprint "MRS25")
      (description "RES 10kΩ 1% 50ppm/K 600mW")
      (fields (field (name "TOLERANCE") "1% + 50ppm/K") (field (name "POWER") "600mW"))
      (libsource (lib "DecadeBox") (part "RES-10KOHM"))
    )
    (comp (ref "R128")
      (value "10kΩ")
      (footprint "MRS25")
      (description "RES 10kΩ 1% 50ppm/K 600mW")
      (fields (field (name "TOLERANCE") "1% + 50ppm/K") (field (name "POWER") "600mW"))
      (libsource (lib "DecadeBox") (part "RES-10KOHM"))
    )
    (comp (ref "R129")
      (value "100kΩ")
      (footprint "MRS25")
      (description "RES 100kΩ 1% 50ppm/K 600mW")
      (fields (field (name "TOLERANCE") "1% + 50ppm/K") (field (name "POWER") "600mW"))
      (libsource (lib "DecadeBox") (part "RES-100KOHM"))
    )
    (comp (ref "R130")
      (value "100kΩ")
      (footprint "MRS25")
      (description "RES 100kΩ 1% 50ppm/K 600mW")
      (fields (field (name "TOLERANCE") "1% + 50ppm/K") (field (name "POWER") "600mW"))
      (libsource (lib "DecadeBox") (part "RES-100KOHM"))
    )
    (comp (ref "R131")
      (value "100kΩ")
      (footprint "MRS25")
      (description "RES 100kΩ 1% 50ppm/K 600mW")
      (fields (field (name "TOLERANCE") "1% + 50ppm/K") (field (name "POWER") "600mW"))
      (libsource (lib "DecadeBox") (part "RES-100KOHM"))
    )
    (comp (ref "R132")
      (value "100kΩ")
      (footprint "MRS25")
      (description "RES 100kΩ 1% 50ppm/K 600mW")
      (fields (field (name "TOLERANCE") "1% + 50ppm/K") (field (name "POWER") "600mW"))
      (libsource (lib "DecadeBox") (part "RES-100KOHM"))
    )
    (comp (ref "R133")
      (value "1Ω")
      (footprint "MRS25")
      (description "RES 1Ω 1% 50ppm/K 600mW")
      (fields (field (name "TOLERANCE") "1% + 50ppm/K") (field (name "POWER") "600mW"))
      (libsource (lib "DecadeBox") (part "RES-1OHM"))
    )
    (comp (ref "R134")
      (value "1Ω")
      (footprint "MRS25")
      (description "RES 1Ω 1% 50ppm/K 600mW")
      (fields (field (name "TOLERANCE") "1% + 50ppm/K") (field (name "POWER") "600mW"))
      (libsource (lib "DecadeBox") (part "RES-1OHM"))
    )
    (comp (ref "R135")
      (value "10Ω")
      (footprint "MRS25")
      (description "RES 10Ω 1% 50ppm/K 600mW")
      (fields (field (name "TOLERANCE") "1% + 50ppm/K") (field (name "POWER") "600mW"))
      (libsource (lib "DecadeBox") (part "RES-10OHM"))
    )
    (comp (ref "R136")
      (value "10Ω")
      (footprint "MRS25")
      (description "RES 10Ω 1% 50ppm/K 600mW")
      (fields (field (name "TOLERANCE") "1% + 50ppm/K") (field (name "POWER") "600mW"))
      (libsource (lib "DecadeBox") (part "RES-10OHM"))
    )
    (comp (ref "R137")
      (value "10Ω")
      (footprint "MRS25")
      (description "RES 10Ω 1% 50ppm/K 600mW")
      (fields (field (name "TOLERANCE") "1% + 50ppm/K") (field (name "POWER") "600mW"))
      (libsource (lib "DecadeBox") (part "RES-10OHM"))
    )
    (comp (ref "R138")
      (value "10Ω")
      (footprint "MRS25")
      (description "RES 10Ω 1% 50ppm/K 600mW")
      (fields (field (name "TOLERANCE") "1% + 50ppm/K") (field (name "POWER") "600mW"))
      (libsource (lib "DecadeBox") (part "RES-10OHM"))
    )
    (comp (ref "R139")
      (value "100Ω")
      (footprint "MRS25")
      (description "RES 100Ω 1% 50ppm/K 600mW")
      (fields (field (name "TOLERANCE") "1% + 50ppm/K") (field (name "POWER") "600mW"))
      (libsource (lib "DecadeBox") (part "RES-100OHM"))
    )
    (comp (ref "R140")
      (value "100Ω")
      (footprint "MRS25")
      (description "RES 100Ω 1% 50ppm/K 600mW")
      (fields (field (name "TOLERANCE") "1% + 50ppm/K") (field (name "POWER") "600mW"))
      (libsource (lib "DecadeBox") (part "RES-100OHM"))
    )
    (comp (ref "R141")
      (value "1kΩ")
      (footprint "MRS25")
      (description "RES 1kΩ 1% 50ppm/K 600mW")
      (fields (field (name "TOLERANCE") "1% + 50ppm/K") (field (name "POWER") "600mW"))
      (libsource (lib "DecadeBox") (part "RES-1KOHM"))
    )
    (comp (ref "R142")
      (value "1kΩ")
      (footprint "MRS25")
      (description "RES 1kΩ 1% 50ppm/K 600mW")
      (fields (field (name "TOLERANCE") "1% + 50ppm/K") (field (name "POWER") "600mW"))
      (libsource (lib "DecadeBox") (part "RES-1KOHM"))
    )
    (comp (ref "R143")
      (value "1kΩ")
      (footprint "MRS25")
      (description "RES 1kΩ 1% 50ppm/K 600mW")
      (fields (field (name "TOLERANCE") "1% + 50ppm/K") (field (name "POWER") "600mW"))
      (libsource (lib "DecadeBox") (part "RES-1KOHM"))
    )
    (comp (ref "R144")
      (value "1kΩ")
      (footprint "MRS25")
      (description "RES 1kΩ 1% 50ppm/K 600mW")
      (fields (field (name "TOLERANCE") "1% + 50ppm/K") (field (name "POWER") "600mW"))
      (libsource (lib "DecadeBox") (part "RES-1KOHM"))
    )
    (comp (ref "R145")
      (value "10kΩ")
      (footprint "MRS25")
      (description "RES 10kΩ 1% 50ppm/K 600mW")
      (fields (field (name "TOLERANCE") "1% + 50ppm/K") (field (name "POWER") "600mW"))
      (libsource (lib "DecadeBox") (part "RES-10KOHM"))
    )
    (comp (ref "R146")
      (value "10kΩ")
      (footprint "MRS25")
      (description "RES 10kΩ 1% 50ppm/K 600mW")
      (fields (field (name "TOLERANCE") "1% + 50ppm/K") (field (name "POWER") "600mW"))
      (libsource (lib "DecadeBox") (part "RES-10KOHM"))
    )
    (comp (ref "R147")
      (value "10kΩ")
      (footprint "MRS25")
      (description "RES 10kΩ 1% 50ppm/K 600mW")
      (fields (field (name "TOLERANCE") "1% + 50ppm/K") (field (name "POWER") "600mW"))
      (libsource (lib "DecadeBox") (part "RES-10KOHM"))
    )
    (comp (ref "R148")
      (value "10kΩ")
      (footprint "MRS25")
      (description "RES 10kΩ 1% 50ppm/K 600mW")
      (fields (field (name "TOLERANCE") "1% + 50ppm/K") (field (name "POWER") "600mW"))
      (libsource (lib "DecadeBox") (part "RES-10KOHM"))
    )
    (comp (ref "R149")
      (value "100kΩ")
      (footprint "MRS25")
      (description "RES 100kΩ 1% 50ppm/K 600mW")
      (fields (field (name "TOLERANCE") "1% + 50ppm/K") (field (name "POWER") "600mW"))
      (libsource (lib "DecadeBox") (part "RES-100KOHM"))
    )
    (comp (ref "R150")
      (value "100kΩ")
      (footprint "MRS25")
      (description "RES 100kΩ 1% 50ppm/K 600mW")
      (fields (field (name "TOLERANCE") "1% + 50ppm/K") (field (name "POWER") "600mW"))
      (libsource (lib "DecadeBox") (part "RES-100KOHM"))
    )
    (comp (ref "R151")
      (value "100kΩ")
      (footprint "MRS25")
      (description "RES 100kΩ 1% 50ppm/K 600mW")
      (fields (field (name "TOLERANCE") "1% + 50ppm/K") (field (name "POWER") "600mW"))
      (libsource (lib "DecadeBox") (part "RES-100KOHM"))
    )
    (comp (ref "R152")
      (value "100kΩ")
      (footprint "MRS25")
      (description "RES 100kΩ 1% 50ppm/K 600mW")
      (fields (field (name "TOLERANCE") "1% + 50ppm/K") (field (name "POWER") "600mW"))
      (libsource (lib "DecadeBox") (part "RES-100KOHM"))
    )
    (comp (ref "R153")
      (value "1Ω")
      (footprint "MRS25")
      (description "RES 1Ω 1% 50ppm/K 600mW")
      (fields (field (name "TOLERANCE") "1% + 50ppm/K") (field (name "POWER") "600mW"))
      (libsource (lib "DecadeBox") (part "RES-1OHM"))
    )
    (comp (ref "R154")
      (value "1Ω")
      (footprint "MRS25")
      (description "RES 1Ω 1% 50ppm/K 600mW")
      (fields (field (name "TOLERANCE") "1% + 50ppm/K") (field (name "POWER") "600mW"))
      (libsource (lib "DecadeBox") (part "RES-1OHM"))
    )
    (comp (ref "R155")
      (value "10Ω")
      (footprint "MRS25")
      (description "RES 10Ω 1% 50ppm/K 600mW")
      (fields (field (name "TOLERANCE") "1% + 50ppm/K") (field (name "POWER") "600mW"))
      (libsource (lib "DecadeBox") (part "RES-10OHM"))
    )
    (comp (ref "R156")
      (value "10Ω")
      (footprint "MRS25")
      (description "RES 10Ω 1% 50ppm/K 600mW")
      (fields (field (name "TOLERANCE") "1% + 50ppm/K") (field (name "POWER") "600mW"))
      (libsource (lib "DecadeBox") (part "RES-10OHM"))
    )
    (comp (ref "R157")
      (value "10Ω")
      (footprint "MRS25")
      (description "RES 10Ω 1% 50ppm/K 600mW")
      (fields (field (name "TOLERANCE") "1% + 50ppm/K") (field (name "POWER") "600mW"))
      (libsource (lib "DecadeBox") (part "RES-10OHM"))
    )
    (comp (ref "R158")
      (value "10Ω")
      (footprint "MRS25")
      (description "RES 10Ω 1% 50ppm/K 600mW")
      (fields (field (name "TOLERANCE") "1% + 50ppm/K") (field (name "POWER") "600mW"))
      (libsource (lib "DecadeBox") (part "RES-10OHM"))
    )
    (comp (ref "R159")
      (value "100Ω")
      (footprint "MRS25")
      (description "RES 100Ω 1% 50ppm/K 600mW")
      (fields (field (name "TOLERANCE") "1% + 50ppm/K") (field (name "POWER") "600mW"))
      (libsource (lib "DecadeBox") (part "RES-100OHM"))
    )
    (comp (ref "R160")
      (value "100Ω")
      (footprint "MRS25")
      (description "RES 100Ω 1% 50ppm/K 600mW")
      (fields (field (name "TOLERANCE") "1% + 50ppm/K") (field (name "POWER") "600mW"))
      (libsource (lib "DecadeBox") (part "RES-100OHM"))
    )
    (comp (ref "R161")
      (value "1kΩ")
      (footprint "MRS25")
      (description "RES 1kΩ 1% 50ppm/K 600mW")
      (fields (field (name "TOLERANCE") "1% + 50ppm/K") (field (name "POWER") "600mW"))
      (libsource (lib "DecadeBox") (part "RES-1KOHM"))
    )
    (comp (ref "R162")
      (value "1kΩ")
      (footprint "MRS25")
      (description "RES 1kΩ 1% 50ppm/K 600mW")
      (fields (field (name "TOLERANCE") "1% + 50ppm/K") (field (name "POWER") "600mW"))
      (libsource (lib "DecadeBox") (part "RES-1KOHM"))
    )
    (comp (ref "R163")
      (value "10kΩ")
      (footprint "MRS25")
      (description "RES 10kΩ 1% 50ppm/K 600mW")
      (fields (field (name "TOLERANCE") "1% + 50ppm/K") (field (name "POWER") "600mW"))
      (libsource (lib "DecadeBox") (part "RES-10KOHM"))
    )
    (comp (ref "R164")
      (value "10kΩ")
      (footprint "MRS25")
      (description "RES 10kΩ 1% 50ppm/K 600mW")
      (fields (field (name "TOLERANCE") "1% + 50ppm/K") (field (name "POWER") "600mW"))
      (libsource (lib "DecadeBox") (part "RES-10KOHM"))
    )
    (comp (ref "R165")
      (value "100kΩ")
      (footprint "MRS25")
      (description "RES 100kΩ 1% 50ppm/K 600mW")
      (fields (field (name "TOLERANCE") "1% + 50ppm/K") (field (name "POWER") "600mW"))
      (libsource (lib "DecadeBox") (part "RES-100KOHM"))
    )
    (comp (ref "R166")
      (value "100kΩ")
      (footprint "MRS25")
      (description "RES 100kΩ 1% 50ppm/K 600mW")
      (fields (field (name "TOLERANCE") "1% + 50ppm/K") (field (name "POWER") "600mW"))
      (libsource (lib "DecadeBox") (part "RES-100KOHM"))
    )
    (comp (ref "R167")
      (value "1Ω")
      (footprint "MRS25")
      (description "RES 1Ω 1% 50ppm/K 600mW")
      (fields (field (name "TOLERANCE") "1% + 50ppm/K") (field (name "POWER") "600mW"))
      (libsource (lib "DecadeBox") (part "RES-1OHM"))
    )
    (comp (ref "R168")
      (value "1Ω")
      (footprint "MRS25")
      (description "RES 1Ω 1% 50ppm/K 600mW")
      (fields (field (name "TOLERANCE") "1% + 50ppm/K") (field (name "POWER") "600mW"))
      (libsource (lib "DecadeBox") (part "RES-1OHM"))
    )
    (comp (ref "R169")
      (value "10Ω")
      (footprint "MRS25")
      (description "RES 10Ω 1% 50ppm/K 600mW")
      (fields (field (name "TOLERANCE") "1% + 50ppm/K") (field (name "POWER") "600mW"))
      (libsource (lib "DecadeBox") (part "RES-10OHM"))
    )
    (comp (ref "R170")
      (value "10Ω")
      (footprint "MRS25")
      (description "RES 10Ω 1% 50ppm/K 600mW")
      (fields (field (name "TOLERANCE") "1% + 50ppm/K") (field (name "POWER") "600mW"))
      (libsource (lib "DecadeBox") (part "RES-10OHM"))
    )
    (comp (ref "R171")
      (value "10Ω")
      (footprint "MRS25")
      (description "RES 10Ω 1% 50ppm/K 600mW")
      (fields (field (name "TOLERANCE") "1% + 50ppm/K") (field (name "POWER") "600mW"))
      (libsource (lib "DecadeBox") (part "RES-10OHM"))
    )
    (comp (ref "R172")
      (value "10Ω")
      (footprint "MRS25")
      (description "RES 10Ω 1% 50ppm/K 600mW")
      (fields (field (name "TOLERANCE") "1% + 50ppm/K") (field (name "POWER") "600mW"))
      (libsource (lib "DecadeBox") (part "RES-10OHM"))
    )
    (comp (ref "R173")
      (value "100Ω")
      (footprint "MRS25")
      (description "RES 100Ω 1% 50ppm/K 600mW")
      (fields (field (name "TOLERANCE") "1% + 50ppm/K") (field (name "POWER") "600mW"))
      (libsource (lib "DecadeBox") (part "RES-100OHM"))
    )
    (comp (ref "R174")
      (value "100Ω")
      (footprint "MRS25")
      (description "RES 100Ω 1% 50ppm/K 600mW")
      (fields (field (name "TOLERANCE") "1% + 50ppm/K") (field (name "POWER") "600mW"))
      (libsource (lib "DecadeBox") (part "RES-100OHM"))
    )
    (comp (ref "R175")
      (value "1kΩ")
      (footprint "MRS25")
      (description "RES 1kΩ 1% 50ppm/K 600mW")
      (fields (field (name "TOLERANCE") "1% + 50ppm/K") (field (name "POWER") "600mW"))
      (libsource (lib "DecadeBox") (part "RES-1KOHM"))
    )
    (comp (ref "R176")
      (value "1kΩ")
      (footprint "MRS25")
      (description "RES 1kΩ 1% 50ppm/K 600mW")
      (fields (field (name "TOLERANCE") "1% + 50ppm/K") (field (name "POWER") "600mW"))
      (libsource (lib "DecadeBox") (part "RES-1KOHM"))
    )
    (comp (ref "R177")
      (value "10kΩ")
      (footprint "MRS25")
      (description "RES 10kΩ 1% 50ppm/K 600mW")
      (fields (field (name "TOLERANCE") "1% + 50ppm/K") (field (name "POWER") "600mW"))
      (libsource (lib "DecadeBox") (part "RES-10KOHM"))
    )
    (comp (ref "R178")
      (value "10kΩ")
      (footprint "MRS25")
      (description "RES 10kΩ 1% 50ppm/K 600mW")
      (fields (field (name "TOLERANCE") "1% + 50ppm/K") (field (name "POWER") "600mW"))
      (libsource (lib "DecadeBox") (part "RES-10KOHM"))
    )
    (comp (ref "R179")
      (value "100kΩ")
      (footprint "MRS25")
      (description "RES 100kΩ 1% 50ppm/K 600mW")
      (fields (field (name "TOLERANCE") "1% + 50ppm/K") (field (name "POWER") "600mW"))
      (libsource (lib "DecadeBox") (part "RES-100KOHM"))
    )
    (comp (ref "R180")
      (value "100kΩ")
      (footprint "MRS25")
      (description "RES 100kΩ 1% 50ppm/K 600mW")
      (fields (field (name "TOLERANCE") "1% + 50ppm/K") (field (name "POWER") "600mW"))
      (libsource (lib "DecadeBox") (part "RES-100KOHM"))
    )
    (comp (ref "R181")
      (value "1Ω")
      (footprint "MRS25")
      (description "RES 1Ω 1% 50ppm/K 600mW")
      (fields (field (name "TOLERANCE") "1% + 50ppm/K") (field (name "POWER") "600mW"))
      (libsource (lib "DecadeBox") (part "RES-1OHM"))
    )
    (comp (ref "R182")
      (value "1Ω")
      (footprint "MRS25")
      (description "RES 1Ω 1% 50ppm/K 600mW")
      (fields (field (name "TOLERANCE") "1% + 50ppm/K") (field (name "POWER") "600mW"))
      (libsource (lib "DecadeBox") (part "RES-1OHM"))
    )
    (comp (ref "R183")
      (value "10Ω")
      (footprint "MRS25")
      (description "RES 10Ω 1% 50ppm/K 600mW")
      (fields (field (name "TOLERANCE") "1% + 50ppm/K") (field (name "POWER") "600mW"))
      (libsource (lib "DecadeBox") (part "RES-10OHM"))
    )
    (comp (ref "R184")
      (value "10Ω")
      (footprint "MRS25")
      (description "RES 10Ω 1% 50ppm/K 600mW")
      (fields (field (name "TOLERANCE") "1% + 50ppm/K") (field (name "POWER") "600mW"))
      (libsource (lib "DecadeBox") (part "RES-10OHM"))
    )
    (comp (ref "R185")
      (value "10Ω")
      (footprint "MRS25")
      (description "RES 10Ω 1% 50ppm/K 600mW")
      (fields (field (name "TOLERANCE") "1% + 50ppm/K") (field (name "POWER") "600mW"))
      (libsource (lib "DecadeBox") (part "RES-10OHM"))
    )
    (comp (ref "R186")
      (value "10Ω")
      (footprint "MRS25")
      (description "RES 10Ω 1% 50ppm/K 600mW")
      (fields (field (name "TOLERANCE") "1% + 50ppm/K") (field (name "POWER") "600mW"))
      (libsource (lib "DecadeBox") (part "RES-10OHM"))
    )
    (comp (ref "R187")
      (value "100Ω")
      (footprint "MRS25")
      (description "RES 100Ω 1% 50ppm/K 600mW")
      (fields (field (name "TOLERANCE") "1% + 50ppm/K") (field (name "POWER") "600mW"))
      (libsource (lib "DecadeBox") (part "RES-100OHM"))
    )
    (comp (ref "R188")
      (value "100Ω")
      (footprint "MRS25")
      (description "RES 100Ω 1% 50ppm/K 600mW")
      (fields (field (name "TOLERANCE") "1% + 50ppm/K") (field (name "POWER") "600mW"))
      (libsource (lib "DecadeBox") (part "RES-100OHM"))
    )
    (comp (ref "R189")
      (value "1Ω")
      (footprint "MRS25")
      (description "RES 1Ω 1% 50ppm/K 600mW")
      (fields (field (name "TOLERANCE") "1% + 50ppm/K") (field (name "POWER") "600mW"))
      (libsource (lib "DecadeBox") (part "RES-1OHM"))
    )
    (comp (ref "R190")
      (value "1Ω")
      (footprint "MRS25")
      (description "RES 1Ω 1% 50ppm/K 600mW")
      (fields (field (name "TOLERANCE") "1% + 50ppm/K") (field (name "POWER") "600mW"))
      (libsource (lib "DecadeBox") (part "RES-1OHM"))
    )
    (comp (ref "R191")
      (value "10Ω")
      (footprint "MRS25")
      (description "RES 10Ω 1% 50ppm/K 600mW")
      (fields (field (name "TOLERANCE") "1% + 50ppm/K") (field (name "POWER") "600mW"))
      (libsource (lib "DecadeBox") (part "RES-10OHM"))
    )
    (comp (ref "R192")
      (value "10Ω")
      (footprint "MRS25")
      (description "RES 10Ω 1% 50ppm/K 600mW")
      (fields (field (name "TOLERANCE") "1% + 50ppm/K") (field (name "POWER") "600mW"))
      (libsource (lib "DecadeBox") (part "RES-10OHM"))
    )
    (comp (ref "R193")
      (value "10Ω")
      (footprint "MRS25")
      (description "RES 10Ω 1% 50ppm/K 600mW")
      (fields (field (name "TOLERANCE") "1% + 50ppm/K") (field (name "POWER") "600mW"))
      (libsource (lib "DecadeBox") (part "RES-10OHM"))
    )
    (comp (ref "R194")
      (value "10Ω")
      (footprint "MRS25")
      (description "RES 10Ω 1% 50ppm/K 600mW")
      (fields (field (name "TOLERANCE") "1% + 50ppm/K") (field (name "POWER") "600mW"))
      (libsource (lib "DecadeBox") (part "RES-10OHM"))
    )
    (comp (ref "R195")
      (value "100Ω")
      (footprint "MRS25")
      (description "RES 100Ω 1% 50ppm/K 600mW")
      (fields (field (name "TOLERANCE") "1% + 50ppm/K") (field (name "POWER") "600mW"))
      (libsource (lib "DecadeBox") (part "RES-100OHM"))
    )
    (comp (ref "R196")
      (value "100Ω")
      (footprint "MRS25")
      (description "RES 100Ω 1% 50ppm/K 600mW")
      (fields (field (name "TOLERANCE") "1% + 50ppm/K") (field (name "POWER") "600mW"))
      (libsource (lib "DecadeBox") (part "RES-100OHM"))
    )
    (comp (ref "R197")
      (value "1Ω")
      (footprint "MRS25")
      (description "RES 1Ω 1% 50ppm/K 600mW")
      (fields (field (name "TOLERANCE") "1% + 50ppm/K") (field (name "POWER") "600mW"))
      (libsource (lib "DecadeBox") (part "RES-1OHM"))
    )
    (comp (ref "R198")
      (value "1Ω")
      (footprint "MRS25")
      (description "RES 1Ω 1% 50ppm/K 600mW")
      (fields (field (name "TOLERANCE") "1% + 50ppm/K") (field (name "POWER") "600mW"))
      (libsource (lib "DecadeBox") (part "RES-1OHM"))
    )
    (comp (ref "R199")
      (value "10Ω")
      (footprint "MRS25")
      (description "RES 10Ω 1% 50ppm/K 600mW")
      (fields (field (name "TOLERANCE") "1% + 50ppm/K") (field (name "POWER") "600mW"))
      (libsource (lib "DecadeBox") (part "RES-10OHM"))
    )
    (comp (ref "R200")
      (value "10Ω")
      (footprint "MRS25")
      (description "RES 10Ω 1% 50ppm/K 600mW")
      (fields (field (name "TOLERANCE") "1% + 50ppm/K") (field (name "POWER") "600mW"))
      (libsource (lib "DecadeBox") (part "RES-10OHM"))
    )
    (comp (ref "R201")
      (value "10Ω")
      (footprint "MRS25")
      (description "RES 10Ω 1% 50ppm/K 600mW")
      (fields (field (name "TOLERANCE") "1% + 50ppm/K") (field (name "POWER") "600mW"))
      (libsource (lib "DecadeBox") (part "RES-10OHM"))
    )
    (comp (ref "R202")
      (value "10Ω")
      (footprint "MRS25")
      (description "RES 10Ω 1% 50ppm/K 600mW")
      (fields (field (name "TOLERANCE") "1% + 50ppm/K") (field (name "POWER") "600mW"))
      (libsource (lib "DecadeBox") (part "RES-10OHM"))
    )
    (comp (ref "R203")
      (value "100Ω")
      (footprint "MRS25")
      (description "RES 100Ω 1% 50ppm/K 600mW")
      (fields (field (name "TOLERANCE") "1% + 50ppm/K") (field (name "POWER") "600mW"))
      (libsource (lib "DecadeBox") (part "RES-100OHM"))
    )
    (comp (ref "R204")
      (value "100Ω")
      (footprint "MRS25")
      (description "RES 100Ω 1% 50ppm/K 600mW")
      (fields (field (name "TOLERANCE") "1% + 50ppm/K") (field (name "POWER") "600mW"))
      (libsource (lib "DecadeBox") (part "RES-100OHM"))
    )
    (comp (ref "R205")
      (value "100Ω")
      (footprint "MRS25")
      (description "RES 100Ω 1% 50ppm/K 600mW")
      (fields (field (name "TOLERANCE") "1% + 50ppm/K") (field (name "POWER") "600mW"))
      (libsource (lib "DecadeBox") (part "RES-100OHM"))
    )
    (comp (ref "R206")
      (value "100Ω")
      (footprint "MRS25")
      (description "RES 100Ω 1% 50ppm/K 600mW")
      (fields (field (name "TOLERANCE") "1% + 50ppm/K") (field (name "POWER") "600mW"))
      (libsource (lib "DecadeBox") (part "RES-100OHM"))
    )
    (comp (ref "R207")
      (value "1Ω")
      (footprint "MRS25")
      (description "RES 1Ω 1% 50ppm/K 600mW")
      (fields (field (name "TOLERANCE") "1% + 50ppm/K") (field (name "POWER") "600mW"))
      (libsource (lib "DecadeBox") (part "RES-1OHM"))
    )
    (comp (ref "R208")
      (value "1Ω")
      (footprint "MRS25")
      (description "RES 1Ω 1% 50ppm/K 600mW")
      (fields (field (name "TOLERANCE") "1% + 50ppm/K") (field (name "POWER") "600mW"))
      (libsource (lib "DecadeBox") (part "RES-1OHM"))
    )
    (comp (ref "R209")
      (value "10Ω")
      (footprint "MRS25")
      (description "RES 10Ω 1% 50ppm/K 600mW")
      (fields (field (name "TOLERANCE") "1% + 50ppm/K") (field (name "POWER") "600mW"))
      (libsource (lib "DecadeBox") (part "RES-10OHM"))
    )
    (comp (ref "R210")
      (value "10Ω")
      (footprint "MRS25")
      (description "RES 10Ω 1% 50ppm/K 600mW")
      (fields (field (name "TOLERANCE") "1% + 50ppm/K") (field (name "POWER") "600mW"))
      (libsource (lib "DecadeBox") (part "RES-10OHM"))
    )
    (comp (ref "R211")
      (value "10Ω")
      (footprint "MRS25")
      (description "RES 10Ω 1% 50ppm/K 600mW")
      (fields (field (name "TOLERANCE") "1% + 50ppm/K") (field (name "POWER") "600mW"))
      (libsource (lib "DecadeBox") (part "RES-10OHM"))
    )
    (comp (ref "R212")
      (value "10Ω")
      (footprint "MRS25")
      (description "RES 10Ω 1% 50ppm/K 600mW")
      (fields (field (name "TOLERANCE") "1% + 50ppm/K") (field (name "POWER") "600mW"))
      (libsource (lib "DecadeBox") (part "RES-10OHM"))
    )
    (comp (ref "R213")
      (value "100Ω")
      (footprint "MRS25")
      (description "RES 100Ω 1% 50ppm/K 600mW")
      (fields (field (name "TOLERANCE") "1% + 50ppm/K") (field (name "POWER") "600mW"))
      (libsource (lib "DecadeBox") (part "RES-100OHM"))
    )
    (comp (ref "R214")
      (value "100Ω")
      (footprint "MRS25")
      (description "RES 100Ω 1% 50ppm/K 600mW")
      (fields (field (name "TOLERANCE") "1% + 50ppm/K") (field (name "POWER") "600mW"))
      (libsource (lib "DecadeBox") (part "RES-100OHM"))
    )
    (comp (ref "R215")
      (value "100Ω")
      (footprint "MRS25")
      (description "RES 100Ω 1% 50ppm/K 600mW")
      (fields (field (name "TOLERANCE") "1% + 50ppm/K") (field (name "POWER") "600mW"))
      (libsource (lib "DecadeBox") (part "RES-100OHM"))
    )
    (comp (ref "R216")
      (value "100Ω")
      (footprint "MRS25")
      (description "RES 100Ω 1% 50ppm/K 600mW")
      (fields (field (name "TOLERANCE") "1% + 50ppm/K") (field (name "POWER") "600mW"))
      (libsource (lib "DecadeBox") (part "RES-100OHM"))
    )
  )
  (nets
    (net (code "1") (name "/P0_1K") (class "Default")
      (node (ref "R175") (pin "2") (pintype "passive"))
      (node (ref "R176") (pin "2") (pintype "passive"))
    )
    (net (code "2") (name "/P0_1R") (class "Default")
      (node (ref "R207") (pin "2") (pintype "passive"))
      (node (ref "R208") (pin "2") (pintype "passive"))
    )
    (net (code "3") (name "/P0_10K") (class "Default")
      (node (ref "R177") (pin "2") (pintype "passive"))
      (node (ref "R178") (pin "2") (pintype "passive"))
    )
    (net (code "4") (name "/P0_10R") (class "Default")
      (node (ref "R115") (pin "1") (pintype "passive"))
      (node (ref "R116") (pin "1") (pintype "passive"))
    )
    (net (code "5") (name "/P0_100K") (class "Default")
      (node (ref "R179") (pin "2") (pintype "passive"))
      (node (ref "R180") (pin "2") (pintype "passive"))
    )
    (net (code "6") (name "/P0_100R") (class "Default")
      (node (ref "R25") (pin "2") (pintype "passive"))
      (node (ref "R26") (pin "2") (pintype "passive"))
    )
    (net (code "7") (name "/P1_1K") (class "Default")
      (node (ref "R141") (pin "2") (pintype "passive"))
      (node (ref "R142") (pin "2") (pintype "passive"))
      (node (ref "R161") (pin "1") (pintype "passive"))
      (node (ref "R162") (pin "1") (pintype "passive"))
    )
    (net (code "8") (name "/P1_1R") (class "Default")
      (node (ref "R189") (pin "2") (pintype "passive"))
      (node (ref "R190") (pin "2") (pintype "passive"))
      (node (ref "R197") (pin "1") (pintype "passive"))
      (node (ref "R198") (pin "1") (pintype "passive"))
    )
    (net (code "9") (name "/P1_10K") (class "Default")
      (node (ref "R145") (pin "2") (pintype "passive"))
      (node (ref "R146") (pin "2") (pintype "passive"))
      (node (ref "R163") (pin "1") (pintype "passive"))
      (node (ref "R164") (pin "1") (pintype "passive"))
    )
    (net (code "10") (name "/P1_10R") (class "Default")
      (node (ref "R135") (pin "2") (pintype "passive"))
      (node (ref "R136") (pin "2") (pintype "passive"))
      (node (ref "R155") (pin "1") (pintype "passive"))
      (node (ref "R156") (pin "1") (pintype "passive"))
    )
    (net (code "11") (name "/P1_100K") (class "Default")
      (node (ref "R149") (pin "2") (pintype "passive"))
      (node (ref "R150") (pin "2") (pintype "passive"))
      (node (ref "R165") (pin "1") (pintype "passive"))
      (node (ref "R166") (pin "1") (pintype "passive"))
    )
    (net (code "12") (name "/P1_100R") (class "Default")
      (node (ref "R5") (pin "1") (pintype "passive"))
      (node (ref "R6") (pin "1") (pintype "passive"))
      (node (ref "R7") (pin "1") (pintype "passive"))
      (node (ref "R8") (pin "1") (pintype "passive"))
    )
    (net (code "13") (name "/P2_1K") (class "Default")
      (node (ref "R101") (pin "2") (pintype "passive"))
      (node (ref "R102") (pin "2") (pintype "passive"))
      (node (ref "R121") (pin "1") (pintype "passive"))
      (node (ref "R122") (pin "1") (pintype "passive"))
    )
    (net (code "14") (name "/P2_1R") (class "Default")
      (node (ref "R167") (pin "2") (pintype "passive"))
      (node (ref "R168") (pin "2") (pintype "passive"))
      (node (ref "R181") (pin "1") (pintype "passive"))
      (node (ref "R182") (pin "1") (pintype "passive"))
    )
    (net (code "15") (name "/P2_10K") (class "Default")
      (node (ref "R105") (pin "2") (pintype "passive"))
      (node (ref "R106") (pin "2") (pintype "passive"))
      (node (ref "R125") (pin "1") (pintype "passive"))
      (node (ref "R126") (pin "1") (pintype "passive"))
    )
    (net (code "16") (name "/P2_10R") (class "Default")
      (node (ref "R169") (pin "2") (pintype "passive"))
      (node (ref "R170") (pin "2") (pintype "passive"))
      (node (ref "R183") (pin "1") (pintype "passive"))
      (node (ref "R184") (pin "1") (pintype "passive"))
    )
    (net (code "17") (name "/P2_100K") (class "Default")
      (node (ref "R109") (pin "2") (pintype "passive"))
      (node (ref "R110") (pin "2") (pintype "passive"))
      (node (ref "R129") (pin "1") (pintype "passive"))
      (node (ref "R130") (pin "1") (pintype "passive"))
    )
    (net (code "18") (name "/P2_100R") (class "Default")
      (node (ref "R27") (pin "2") (pintype "passive"))
      (node (ref "R28") (pin "2") (pintype "passive"))
      (node (ref "R45") (pin "1") (pintype "passive"))
      (node (ref "R46") (pin "1") (pintype "passive"))
    )
    (net (code "19") (name "/P3_1K") (class "Default")
      (node (ref "R65") (pin "2") (pintype "passive"))
      (node (ref "R66") (pin "2") (pintype "passive"))
      (node (ref "R83") (pin "1") (pintype "passive"))
      (node (ref "R84") (pin "1") (pintype "passive"))
    )
    (net (code "20") (name "/P3_1R") (class "Default")
      (node (ref "R133") (pin "2") (pintype "passive"))
      (node (ref "R134") (pin "2") (pintype "passive"))
      (node (ref "R153") (pin "1") (pintype "passive"))
      (node (ref "R154") (pin "1") (pintype "passive"))
    )
    (net (code "21") (name "/P3_10K") (class "Default")
      (node (ref "R69") (pin "2") (pintype "passive"))
      (node (ref "R70") (pin "2") (pintype "passive"))
      (node (ref "R87") (pin "1") (pintype "passive"))
      (node (ref "R88") (pin "1") (pintype "passive"))
    )
    (net (code "22") (name "/P3_10R") (class "Default")
      (node (ref "R191") (pin "2") (pintype "passive"))
      (node (ref "R192") (pin "2") (pintype "passive"))
      (node (ref "R199") (pin "1") (pintype "passive"))
      (node (ref "R200") (pin "1") (pintype "passive"))
    )
    (net (code "23") (name "/P3_100K") (class "Default")
      (node (ref "R73") (pin "2") (pintype "passive"))
      (node (ref "R74") (pin "2") (pintype "passive"))
      (node (ref "R91") (pin "1") (pintype "passive"))
      (node (ref "R92") (pin "1") (pintype "passive"))
    )
    (net (code "24") (name "/P3_100R") (class "Default")
      (node (ref "R63") (pin "2") (pintype "passive"))
      (node (ref "R64") (pin "2") (pintype "passive"))
      (node (ref "R81") (pin "1") (pintype "passive"))
      (node (ref "R82") (pin "1") (pintype "passive"))
    )
    (net (code "25") (name "/P4_1K") (class "Default")
      (node (ref "R29") (pin "2") (pintype "passive"))
      (node (ref "R30") (pin "2") (pintype "passive"))
      (node (ref "R47") (pin "1") (pintype "passive"))
      (node (ref "R48") (pin "1") (pintype "passive"))
    )
    (net (code "26") (name "/P4_1R") (class "Default")
      (node (ref "R113") (pin "1") (pintype "passive"))
      (node (ref "R114") (pin "1") (pintype "passive"))
      (node (ref "R95") (pin "2") (pintype "passive"))
      (node (ref "R96") (pin "2") (pintype "passive"))
    )
    (net (code "27") (name "/P4_10K") (class "Default")
      (node (ref "R33") (pin "2") (pintype "passive"))
      (node (ref "R34") (pin "2") (pintype "passive"))
      (node (ref "R51") (pin "1") (pintype "passive"))
      (node (ref "R52") (pin "1") (pintype "passive"))
    )
    (net (code "28") (name "/P4_10R") (class "Default")
      (node (ref "R209") (pin "2") (pintype "passive"))
      (node (ref "R210") (pin "2") (pintype "passive"))
      (node (ref "R211") (pin "2") (pintype "passive"))
      (node (ref "R212") (pin "2") (pintype "passive"))
    )
    (net (code "29") (name "/P4_100K") (class "Default")
      (node (ref "R37") (pin "2") (pintype "passive"))
      (node (ref "R38") (pin "2") (pintype "passive"))
      (node (ref "R55") (pin "1") (pintype "passive"))
      (node (ref "R56") (pin "1") (pintype "passive"))
    )
    (net (code "30") (name "/P4_100R") (class "Default")
      (node (ref "R100") (pin "2") (pintype "passive"))
      (node (ref "R119") (pin "1") (pintype "passive"))
      (node (ref "R120") (pin "1") (pintype "passive"))
      (node (ref "R99") (pin "2") (pintype "passive"))
    )
    (net (code "31") (name "/P5_1K") (class "Default")
      (node (ref "R10") (pin "1") (pintype "passive"))
      (node (ref "R11") (pin "1") (pintype "passive"))
      (node (ref "R12") (pin "1") (pintype "passive"))
      (node (ref "R9") (pin "1") (pintype "passive"))
    )
    (net (code "32") (name "/P5_1R") (class "Default")
      (node (ref "R59") (pin "2") (pintype "passive"))
      (node (ref "R60") (pin "2") (pintype "passive"))
      (node (ref "R77") (pin "1") (pintype "passive"))
      (node (ref "R78") (pin "1") (pintype "passive"))
    )
    (net (code "33") (name "/P5_10K") (class "Default")
      (node (ref "R13") (pin "1") (pintype "passive"))
      (node (ref "R14") (pin "1") (pintype "passive"))
      (node (ref "R15") (pin "1") (pintype "passive"))
      (node (ref "R16") (pin "1") (pintype "passive"))
    )
    (net (code "34") (name "/P5_10R") (class "Default")
      (node (ref "R193") (pin "2") (pintype "passive"))
      (node (ref "R194") (pin "2") (pintype "passive"))
      (node (ref "R201") (pin "1") (pintype "passive"))
      (node (ref "R202") (pin "1") (pintype "passive"))
    )
    (net (code "35") (name "/P5_100K") (class "Default")
      (node (ref "R17") (pin "1") (pintype "passive"))
      (node (ref "R18") (pin "1") (pintype "passive"))
      (node (ref "R19") (pin "1") (pintype "passive"))
      (node (ref "R20") (pin "1") (pintype "passive"))
    )
    (net (code "36") (name "/P5_100R") (class "Default")
      (node (ref "R139") (pin "2") (pintype "passive"))
      (node (ref "R140") (pin "2") (pintype "passive"))
      (node (ref "R159") (pin "1") (pintype "passive"))
      (node (ref "R160") (pin "1") (pintype "passive"))
    )
    (net (code "37") (name "/P6_1K") (class "Default")
      (node (ref "R31") (pin "2") (pintype "passive"))
      (node (ref "R32") (pin "2") (pintype "passive"))
      (node (ref "R49") (pin "1") (pintype "passive"))
      (node (ref "R50") (pin "1") (pintype "passive"))
    )
    (net (code "38") (name "/P6_1R") (class "Default")
      (node (ref "R21") (pin "2") (pintype "passive"))
      (node (ref "R22") (pin "2") (pintype "passive"))
      (node (ref "R41") (pin "1") (pintype "passive"))
      (node (ref "R42") (pin "1") (pintype "passive"))
    )
    (net (code "39") (name "/P6_10K") (class "Default")
      (node (ref "R35") (pin "2") (pintype "passive"))
      (node (ref "R36") (pin "2") (pintype "passive"))
      (node (ref "R53") (pin "1") (pintype "passive"))
      (node (ref "R54") (pin "1") (pintype "passive"))
    )
    (net (code "40") (name "/P6_10R") (class "Default")
      (node (ref "R171") (pin "2") (pintype "passive"))
      (node (ref "R172") (pin "2") (pintype "passive"))
      (node (ref "R185") (pin "1") (pintype "passive"))
      (node (ref "R186") (pin "1") (pintype "passive"))
    )
    (net (code "41") (name "/P6_100K") (class "Default")
      (node (ref "R39") (pin "2") (pintype "passive"))
      (node (ref "R40") (pin "2") (pintype "passive"))
      (node (ref "R57") (pin "1") (pintype "passive"))
      (node (ref "R58") (pin "1") (pintype "passive"))
    )
    (net (code "42") (name "/P6_100R") (class "Default")
      (node (ref "R173") (pin "2") (pintype "passive"))
      (node (ref "R174") (pin "2") (pintype "passive"))
      (node (ref "R187") (pin "1") (pintype "passive"))
      (node (ref "R188") (pin "1") (pintype "passive"))
    )
    (net (code "43") (name "/P7_1K") (class "Default")
      (node (ref "R67") (pin "2") (pintype "passive"))
      (node (ref "R68") (pin "2") (pintype "passive"))
      (node (ref "R85") (pin "1") (pintype "passive"))
      (node (ref "R86") (pin "1") (pintype "passive"))
    )
    (net (code "44") (name "/P7_1R") (class "Default")
      (node (ref "R1") (pin "1") (pintype "passive"))
      (node (ref "R2") (pin "1") (pintype "passive"))
      (node (ref "R3") (pin "1") (pintype "passive"))
      (node (ref "R4") (pin "1") (pintype "passive"))
    )
    (net (code "45") (name "/P7_10K") (class "Default")
      (node (ref "R71") (pin "2") (pintype "passive"))
      (node (ref "R72") (pin "2") (pintype "passive"))
      (node (ref "R89") (pin "1") (pintype "passive"))
      (node (ref "R90") (pin "1") (pintype "passive"))
    )
    (net (code "46") (name "/P7_10R") (class "Default")
      (node (ref "R137") (pin "2") (pintype "passive"))
      (node (ref "R138") (pin "2") (pintype "passive"))
      (node (ref "R157") (pin "1") (pintype "passive"))
      (node (ref "R158") (pin "1") (pintype "passive"))
    )
    (net (code "47") (name "/P7_100K") (class "Default")
      (node (ref "R75") (pin "2") (pintype "passive"))
      (node (ref "R76") (pin "2") (pintype "passive"))
      (node (ref "R93") (pin "1") (pintype "passive"))
      (node (ref "R94") (pin "1") (pintype "passive"))
    )
    (net (code "48") (name "/P7_100R") (class "Default")
      (node (ref "R195") (pin "2") (pintype "passive"))
      (node (ref "R196") (pin "2") (pintype "passive"))
      (node (ref "R203") (pin "1") (pintype "passive"))
      (node (ref "R204") (pin "1") (pintype "passive"))
    )
    (net (code "49") (name "/P8_1K") (class "Default")
      (node (ref "R103") (pin "2") (pintype "passive"))
      (node (ref "R104") (pin "2") (pintype "passive"))
      (node (ref "R123") (pin "1") (pintype "passive"))
      (node (ref "R124") (pin "1") (pintype "passive"))
    )
    (net (code "50") (name "/P8_1R") (class "Default")
      (node (ref "R23") (pin "2") (pintype "passive"))
      (node (ref "R24") (pin "2") (pintype "passive"))
      (node (ref "R43") (pin "1") (pintype "passive"))
      (node (ref "R44") (pin "1") (pintype "passive"))
    )
    (net (code "51") (name "/P8_10K") (class "Default")
      (node (ref "R107") (pin "2") (pintype "passive"))
      (node (ref "R108") (pin "2") (pintype "passive"))
      (node (ref "R127") (pin "1") (pintype "passive"))
      (node (ref "R128") (pin "1") (pintype "passive"))
    )
    (net (code "52") (name "/P8_10R") (class "Default")
      (node (ref "R117") (pin "1") (pintype "passive"))
      (node (ref "R118") (pin "1") (pintype "passive"))
      (node (ref "R97") (pin "2") (pintype "passive"))
      (node (ref "R98") (pin "2") (pintype "passive"))
    )
    (net (code "53") (name "/P8_100K") (class "Default")
      (node (ref "R111") (pin "2") (pintype "passive"))
      (node (ref "R112") (pin "2") (pintype "passive"))
      (node (ref "R131") (pin "1") (pintype "passive"))
      (node (ref "R132") (pin "1") (pintype "passive"))
    )
    (net (code "54") (name "/P8_100R") (class "Default")
      (node (ref "R213") (pin "2") (pintype "passive"))
      (node (ref "R214") (pin "2") (pintype "passive"))
      (node (ref "R215") (pin "2") (pintype "passive"))
      (node (ref "R216") (pin "2") (pintype "passive"))
    )
    (net (code "55") (name "/P9_1K") (class "Default")
      (node (ref "R143") (pin "2") (pintype "passive"))
      (node (ref "R144") (pin "2") (pintype "passive"))
    )
    (net (code "56") (name "/P9_1R") (class "Default")
      (node (ref "R61") (pin "2") (pintype "passive"))
      (node (ref "R62") (pin "2") (pintype "passive"))
    )
    (net (code "57") (name "/P9_10K") (class "Default")
      (node (ref "R147") (pin "2") (pintype "passive"))
      (node (ref "R148") (pin "2") (pintype "passive"))
    )
    (net (code "58") (name "/P9_10R") (class "Default")
      (node (ref "R79") (pin "1") (pintype "passive"))
      (node (ref "R80") (pin "1") (pintype "passive"))
    )
    (net (code "59") (name "/P9_100K") (class "Default")
      (node (ref "R151") (pin "2") (pintype "passive"))
      (node (ref "R152") (pin "2") (pintype "passive"))
    )
    (net (code "60") (name "/P9_100R") (class "Default")
      (node (ref "R205") (pin "1") (pintype "passive"))
      (node (ref "R206") (pin "1") (pintype "passive"))
    )
    (net (code "61") (name "Net-(R1-Pad2)") (class "Default")
      (node (ref "R1") (pin "2") (pintype "passive"))
      (node (ref "R2") (pin "2") (pintype "passive"))
      (node (ref "R21") (pin "1") (pintype "passive"))
      (node (ref "R22") (pin "1") (pintype "passive"))
    )
    (net (code "62") (name "Net-(R10-Pad2)") (class "Default")
      (node (ref "R10") (pin "2") (pintype "passive"))
      (node (ref "R29") (pin "1") (pintype "passive"))
      (node (ref "R30") (pin "1") (pintype "passive"))
      (node (ref "R9") (pin "2") (pintype "passive"))
    )
    (net (code "63") (name "Net-(R11-Pad2)") (class "Default")
      (node (ref "R11") (pin "2") (pintype "passive"))
      (node (ref "R12") (pin "2") (pintype "passive"))
      (node (ref "R31") (pin "1") (pintype "passive"))
      (node (ref "R32") (pin "1") (pintype "passive"))
    )
    (net (code "64") (name "Net-(R13-Pad2)") (class "Default")
      (node (ref "R13") (pin "2") (pintype "passive"))
      (node (ref "R14") (pin "2") (pintype "passive"))
      (node (ref "R33") (pin "1") (pintype "passive"))
      (node (ref "R34") (pin "1") (pintype "passive"))
    )
    (net (code "65") (name "Net-(R15-Pad2)") (class "Default")
      (node (ref "R15") (pin "2") (pintype "passive"))
      (node (ref "R16") (pin "2") (pintype "passive"))
      (node (ref "R35") (pin "1") (pintype "passive"))
      (node (ref "R36") (pin "1") (pintype "passive"))
    )
    (net (code "66") (name "Net-(R17-Pad2)") (class "Default")
      (node (ref "R17") (pin "2") (pintype "passive"))
      (node (ref "R18") (pin "2") (pintype "passive"))
      (node (ref "R37") (pin "1") (pintype "passive"))
      (node (ref "R38") (pin "1") (pintype "passive"))
    )
    (net (code "67") (name "Net-(R19-Pad2)") (class "Default")
      (node (ref "R19") (pin "2") (pintype "passive"))
      (node (ref "R20") (pin "2") (pintype "passive"))
      (node (ref "R39") (pin "1") (pintype "passive"))
      (node (ref "R40") (pin "1") (pintype "passive"))
    )
    (net (code "68") (name "Net-(R23-Pad1)") (class "Default")
      (node (ref "R23") (pin "1") (pintype "passive"))
      (node (ref "R24") (pin "1") (pintype "passive"))
      (node (ref "R3") (pin "2") (pintype "passive"))
      (node (ref "R4") (pin "2") (pintype "passive"))
    )
    (net (code "69") (name "Net-(R25-Pad1)") (class "Default")
      (node (ref "R25") (pin "1") (pintype "passive"))
      (node (ref "R26") (pin "1") (pintype "passive"))
      (node (ref "R5") (pin "2") (pintype "passive"))
      (node (ref "R6") (pin "2") (pintype "passive"))
    )
    (net (code "70") (name "Net-(R27-Pad1)") (class "Default")
      (node (ref "R27") (pin "1") (pintype "passive"))
      (node (ref "R28") (pin "1") (pintype "passive"))
      (node (ref "R7") (pin "2") (pintype "passive"))
      (node (ref "R8") (pin "2") (pintype "passive"))
    )
    (net (code "71") (name "Net-(R41-Pad2)") (class "Default")
      (node (ref "R41") (pin "2") (pintype "passive"))
      (node (ref "R42") (pin "2") (pintype "passive"))
      (node (ref "R59") (pin "1") (pintype "passive"))
      (node (ref "R60") (pin "1") (pintype "passive"))
    )
    (net (code "72") (name "Net-(R43-Pad2)") (class "Default")
      (node (ref "R43") (pin "2") (pintype "passive"))
      (node (ref "R44") (pin "2") (pintype "passive"))
      (node (ref "R61") (pin "1") (pintype "passive"))
      (node (ref "R62") (pin "1") (pintype "passive"))
    )
    (net (code "73") (name "Net-(R45-Pad2)") (class "Default")
      (node (ref "R45") (pin "2") (pintype "passive"))
      (node (ref "R46") (pin "2") (pintype "passive"))
      (node (ref "R63") (pin "1") (pintype "passive"))
      (node (ref "R64") (pin "1") (pintype "passive"))
    )
    (net (code "74") (name "Net-(R47-Pad2)") (class "Default")
      (node (ref "R47") (pin "2") (pintype "passive"))
      (node (ref "R48") (pin "2") (pintype "passive"))
      (node (ref "R65") (pin "1") (pintype "passive"))
      (node (ref "R66") (pin "1") (pintype "passive"))
    )
    (net (code "75") (name "Net-(R49-Pad2)") (class "Default")
      (node (ref "R49") (pin "2") (pintype "passive"))
      (node (ref "R50") (pin "2") (pintype "passive"))
      (node (ref "R67") (pin "1") (pintype "passive"))
      (node (ref "R68") (pin "1") (pintype "passive"))
    )
    (net (code "76") (name "Net-(R51-Pad2)") (class "Default")
      (node (ref "R51") (pin "2") (pintype "passive"))
      (node (ref "R52") (pin "2") (pintype "passive"))
      (node (ref "R69") (pin "1") (pintype "passive"))
      (node (ref "R70") (pin "1") (pintype "passive"))
    )
    (net (code "77") (name "Net-(R53-Pad2)") (class "Default")
      (node (ref "R53") (pin "2") (pintype "passive"))
      (node (ref "R54") (pin "2") (pintype "passive"))
      (node (ref "R71") (pin "1") (pintype "passive"))
      (node (ref "R72") (pin "1") (pintype "passive"))
    )
    (net (code "78") (name "Net-(R55-Pad2)") (class "Default")
      (node (ref "R55") (pin "2") (pintype "passive"))
      (node (ref "R56") (pin "2") (pintype "passive"))
      (node (ref "R73") (pin "1") (pintype "passive"))
      (node (ref "R74") (pin "1") (pintype "passive"))
    )
    (net (code "79") (name "Net-(R57-Pad2)") (class "Default")
      (node (ref "R57") (pin "2") (pintype "passive"))
      (node (ref "R58") (pin "2") (pintype "passive"))
      (node (ref "R75") (pin "1") (pintype "passive"))
      (node (ref "R76") (pin "1") (pintype "passive"))
    )
    (net (code "80") (name "Net-(R77-Pad2)") (class "Default")
      (node (ref "R77") (pin "2") (pintype "passive"))
      (node (ref "R78") (pin "2") (pintype "passive"))
      (node (ref "R95") (pin "1") (pintype "passive"))
      (node (ref "R96") (pin "1") (pintype "passive"))
    )
    (net (code "81") (name "Net-(R79-Pad2)") (class "Default")
      (node (ref "R79") (pin "2") (pintype "passive"))
      (node (ref "R80") (pin "2") (pintype "passive"))
      (node (ref "R97") (pin "1") (pintype "passive"))
      (node (ref "R98") (pin "1") (pintype "passive"))
    )
    (net (code "82") (name "Net-(R100-Pad1)") (class "Default")
      (node (ref "R100") (pin "1") (pintype "passive"))
      (node (ref "R81") (pin "2") (pintype "passive"))
      (node (ref "R82") (pin "2") (pintype "passive"))
      (node (ref "R99") (pin "1") (pintype "passive"))
    )
    (net (code "83") (name "Net-(R101-Pad1)") (class "Default")
      (node (ref "R101") (pin "1") (pintype "passive"))
      (node (ref "R102") (pin "1") (pintype "passive"))
      (node (ref "R83") (pin "2") (pintype "passive"))
      (node (ref "R84") (pin "2") (pintype "passive"))
    )
    (net (code "84") (name "Net-(R103-Pad1)") (class "Default")
      (node (ref "R103") (pin "1") (pintype "passive"))
      (node (ref "R104") (pin "1") (pintype "passive"))
      (node (ref "R85") (pin "2") (pintype "passive"))
      (node (ref "R86") (pin "2") (pintype "passive"))
    )
    (net (code "85") (name "Net-(R105-Pad1)") (class "Default")
      (node (ref "R105") (pin "1") (pintype "passive"))
      (node (ref "R106") (pin "1") (pintype "passive"))
      (node (ref "R87") (pin "2") (pintype "passive"))
      (node (ref "R88") (pin "2") (pintype "passive"))
    )
    (net (code "86") (name "Net-(R107-Pad1)") (class "Default")
      (node (ref "R107") (pin "1") (pintype "passive"))
      (node (ref "R108") (pin "1") (pintype "passive"))
      (node (ref "R89") (pin "2") (pintype "passive"))
      (node (ref "R90") (pin "2") (pintype "passive"))
    )
    (net (code "87") (name "Net-(R109-Pad1)") (class "Default")
      (node (ref "R109") (pin "1") (pintype "passive"))
      (node (ref "R110") (pin "1") (pintype "passive"))
      (node (ref "R91") (pin "2") (pintype "passive"))
      (node (ref "R92") (pin "2") (pintype "passive"))
    )
    (net (code "88") (name "Net-(R111-Pad1)") (class "Default")
      (node (ref "R111") (pin "1") (pintype "passive"))
      (node (ref "R112") (pin "1") (pintype "passive"))
      (node (ref "R93") (pin "2") (pintype "passive"))
      (node (ref "R94") (pin "2") (pintype "passive"))
    )
    (net (code "89") (name "Net-(R113-Pad2)") (class "Default")
      (node (ref "R113") (pin "2") (pintype "passive"))
      (node (ref "R114") (pin "2") (pintype "passive"))
      (node (ref "R133") (pin "1") (pintype "passive"))
      (node (ref "R134") (pin "1") (pintype "passive"))
    )
    (net (code "90") (name "Net-(R115-Pad2)") (class "Default")
      (node (ref "R115") (pin "2") (pintype "passive"))
      (node (ref "R116") (pin "2") (pintype "passive"))
      (node (ref "R135") (pin "1") (pintype "passive"))
      (node (ref "R136") (pin "1") (pintype "passive"))
    )
    (net (code "91") (name "Net-(R117-Pad2)") (class "Default")
      (node (ref "R117") (pin "2") (pintype "passive"))
      (node (ref "R118") (pin "2") (pintype "passive"))
      (node (ref "R137") (pin "1") (pintype "passive"))
      (node (ref "R138") (pin "1") (pintype "passive"))
    )
    (net (code "92") (name "Net-(R119-Pad2)") (class "Default")
      (node (ref "R119") (pin "2") (pintype "passive"))
      (node (ref "R120") (pin "2") (pintype "passive"))
      (node (ref "R139") (pin "1") (pintype "passive"))
      (node (ref "R140") (pin "1") (pintype "passive"))
    )
    (net (code "93") (name "Net-(R121-Pad2)") (class "Default")
      (node (ref "R121") (pin "2") (pintype "passive"))
      (node (ref "R122") (pin "2") (pintype "passive"))
      (node (ref "R141") (pin "1") (pintype "passive"))
      (node (ref "R142") (pin "1") (pintype "passive"))
    )
    (net (code "94") (name "Net-(R123-Pad2)") (class "Default")
      (node (ref "R123") (pin "2") (pintype "passive"))
      (node (ref "R124") (pin "2") (pintype "passive"))
      (node (ref "R143") (pin "1") (pintype "passive"))
      (node (ref "R144") (pin "1") (pintype "passive"))
    )
    (net (code "95") (name "Net-(R125-Pad2)") (class "Default")
      (node (ref "R125") (pin "2") (pintype "passive"))
      (node (ref "R126") (pin "2") (pintype "passive"))
      (node (ref "R145") (pin "1") (pintype "passive"))
      (node (ref "R146") (pin "1") (pintype "passive"))
    )
    (net (code "96") (name "Net-(R127-Pad2)") (class "Default")
      (node (ref "R127") (pin "2") (pintype "passive"))
      (node (ref "R128") (pin "2") (pintype "passive"))
      (node (ref "R147") (pin "1") (pintype "passive"))
      (node (ref "R148") (pin "1") (pintype "passive"))
    )
    (net (code "97") (name "Net-(R129-Pad2)") (class "Default")
      (node (ref "R129") (pin "2") (pintype "passive"))
      (node (ref "R130") (pin "2") (pintype "passive"))
      (node (ref "R149") (pin "1") (pintype "passive"))
      (node (ref "R150") (pin "1") (pintype "passive"))
    )
    (net (code "98") (name "Net-(R131-Pad2)") (class "Default")
      (node (ref "R131") (pin "2") (pintype "passive"))
      (node (ref "R132") (pin "2") (pintype "passive"))
      (node (ref "R151") (pin "1") (pintype "passive"))
      (node (ref "R152") (pin "1") (pintype "passive"))
    )
    (net (code "99") (name "Net-(R153-Pad2)") (class "Default")
      (node (ref "R153") (pin "2") (pintype "passive"))
      (node (ref "R154") (pin "2") (pintype "passive"))
      (node (ref "R167") (pin "1") (pintype "passive"))
      (node (ref "R168") (pin "1") (pintype "passive"))
    )
    (net (code "100") (name "Net-(R155-Pad2)") (class "Default")
      (node (ref "R155") (pin "2") (pintype "passive"))
      (node (ref "R156") (pin "2") (pintype "passive"))
      (node (ref "R169") (pin "1") (pintype "passive"))
      (node (ref "R170") (pin "1") (pintype "passive"))
    )
    (net (code "101") (name "Net-(R157-Pad2)") (class "Default")
      (node (ref "R157") (pin "2") (pintype "passive"))
      (node (ref "R158") (pin "2") (pintype "passive"))
      (node (ref "R171") (pin "1") (pintype "passive"))
      (node (ref "R172") (pin "1") (pintype "passive"))
    )
    (net (code "102") (name "Net-(R159-Pad2)") (class "Default")
      (node (ref "R159") (pin "2") (pintype "passive"))
      (node (ref "R160") (pin "2") (pintype "passive"))
      (node (ref "R173") (pin "1") (pintype "passive"))
      (node (ref "R174") (pin "1") (pintype "passive"))
    )
    (net (code "103") (name "Net-(R161-Pad2)") (class "Default")
      (node (ref "R161") (pin "2") (pintype "passive"))
      (node (ref "R162") (pin "2") (pintype "passive"))
      (node (ref "R175") (pin "1") (pintype "passive"))
      (node (ref "R176") (pin "1") (pintype "passive"))
    )
    (net (code "104") (name "Net-(R163-Pad2)") (class "Default")
      (node (ref "R163") (pin "2") (pintype "passive"))
      (node (ref "R164") (pin "2") (pintype "passive"))
      (node (ref "R177") (pin "1") (pintype "passive"))
      (node (ref "R178") (pin "1") (pintype "passive"))
    )
    (net (code "105") (name "Net-(R165-Pad2)") (class "Default")
      (node (ref "R165") (pin "2") (pintype "passive"))
      (node (ref "R166") (pin "2") (pintype "passive"))
      (node (ref "R179") (pin "1") (pintype "passive"))
      (node (ref "R180") (pin "1") (pintype "passive"))
    )
    (net (code "106") (name "Net-(R181-Pad2)") (class "Default")
      (node (ref "R181") (pin "2") (pintype "passive"))
      (node (ref "R182") (pin "2") (pintype "passive"))
      (node (ref "R189") (pin "1") (pintype "passive"))
      (node (ref "R190") (pin "1") (pintype "passive"))
    )
    (net (code "107") (name "Net-(R183-Pad2)") (class "Default")
      (node (ref "R183") (pin "2") (pintype "passive"))
      (node (ref "R184") (pin "2") (pintype "passive"))
      (node (ref "R191") (pin "1") (pintype "passive"))
      (node (ref "R192") (pin "1") (pintype "passive"))
    )
    (net (code "108") (name "Net-(R185-Pad2)") (class "Default")
      (node (ref "R185") (pin "2") (pintype "passive"))
      (node (ref "R186") (pin "2") (pintype "passive"))
      (node (ref "R193") (pin "1") (pintype "passive"))
      (node (ref "R194") (pin "1") (pintype "passive"))
    )
    (net (code "109") (name "Net-(R187-Pad2)") (class "Default")
      (node (ref "R187") (pin "2") (pintype "passive"))
      (node (ref "R188") (pin "2") (pintype "passive"))
      (node (ref "R195") (pin "1") (pintype "passive"))
      (node (ref "R196") (pin "1") (pintype "passive"))
    )
    (net (code "110") (name "Net-(R197-Pad2)") (class "Default")
      (node (ref "R197") (pin "2") (pintype "passive"))
      (node (ref "R198") (pin "2") (pintype "passive"))
      (node (ref "R207") (pin "1") (pintype "passive"))
      (node (ref "R208") (pin "1") (pintype "passive"))
    )
    (net (code "111") (name "Net-(R199-Pad2)") (class "Default")
      (node (ref "R199") (pin "2") (pintype "passive"))
      (node (ref "R200") (pin "2") (pintype "passive"))
      (node (ref "R209") (pin "1") (pintype "passive"))
      (node (ref "R210") (pin "1") (pintype "passive"))
    )
    (net (code "112") (name "Net-(R201-Pad2)") (class "Default")
      (node (ref "R201") (pin "2") (pintype "passive"))
      (node (ref "R202") (pin "2") (pintype "passive"))
      (node (ref "R211") (pin "1") (pintype "passive"))
      (node (ref "R212") (pin "1") (pintype "passive"))
    )
    (net (code "113") (name "Net-(R203-Pad2)") (class "Default")
      (node (ref "R203") (pin "2") (pintype "passive"))
      (node (ref "R204") (pin "2") (pintype "passive"))
      (node (ref "R213") (pin "1") (pintype "passive"))
      (node (ref "R214") (pin "1") (pintype "passive"))
    )
    (net (code "114") (name "Net-(R205-Pad2)") (class "Default")
      (node (ref "R205") (pin "2") (pintype "passive"))
      (node (ref "R206") (pin "2") (pintype "passive"))
      (node (ref "R215") (pin "1") (pintype "passive"))
      (node (ref "R216") (pin "1") (pintype "passive"))
    )
  )
)
